# PCB-E21-CMB6.net
KiCad netlist of a schematic drawn in EAGLE
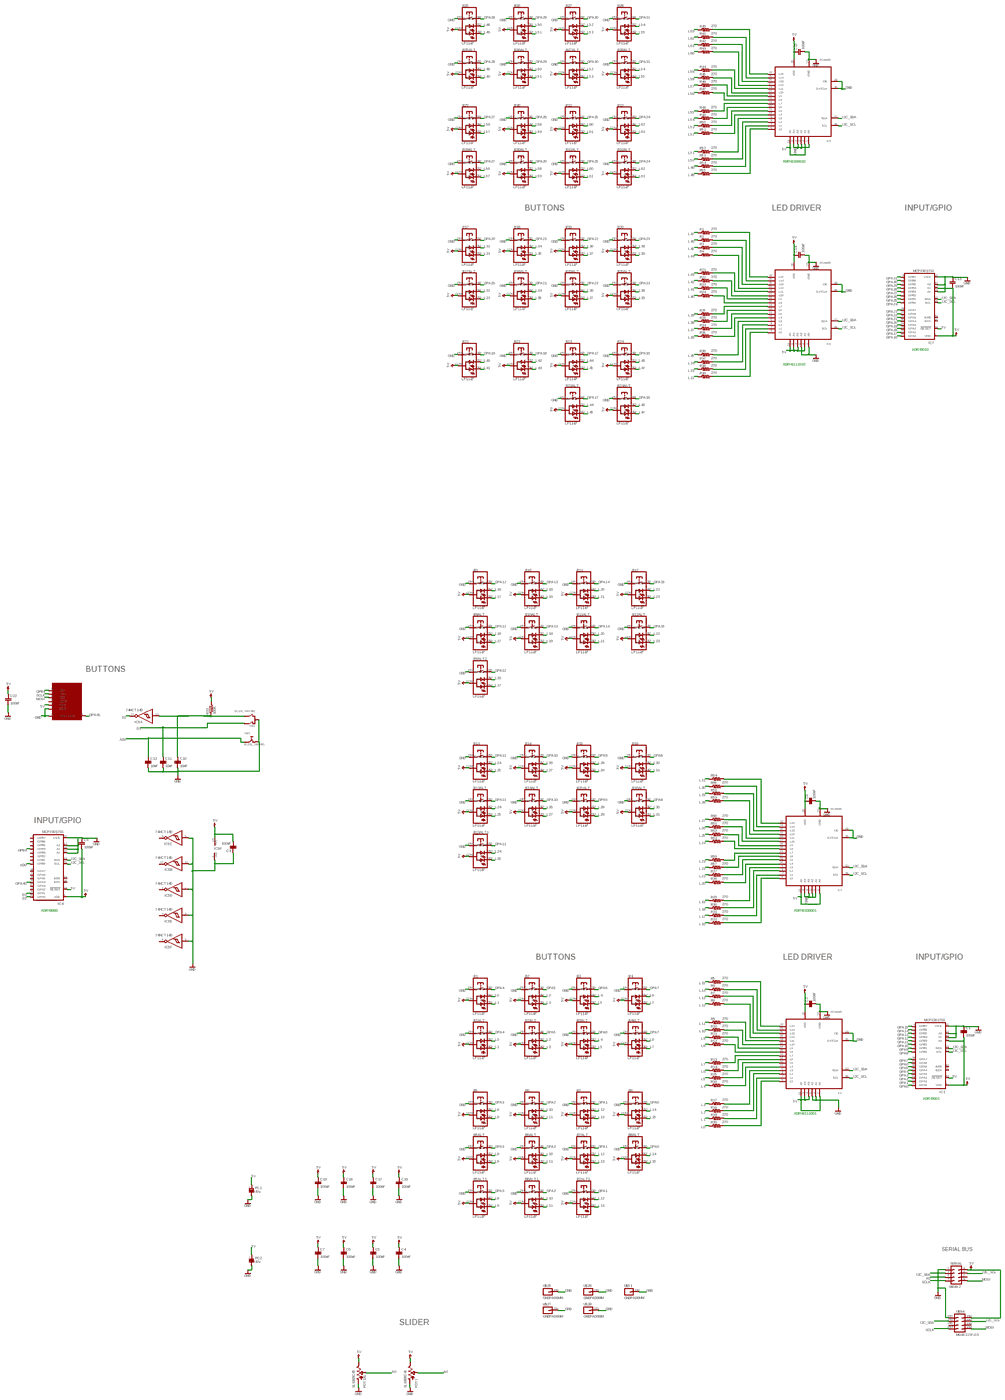
[diagram p0: schematic, sheet 1, overview]
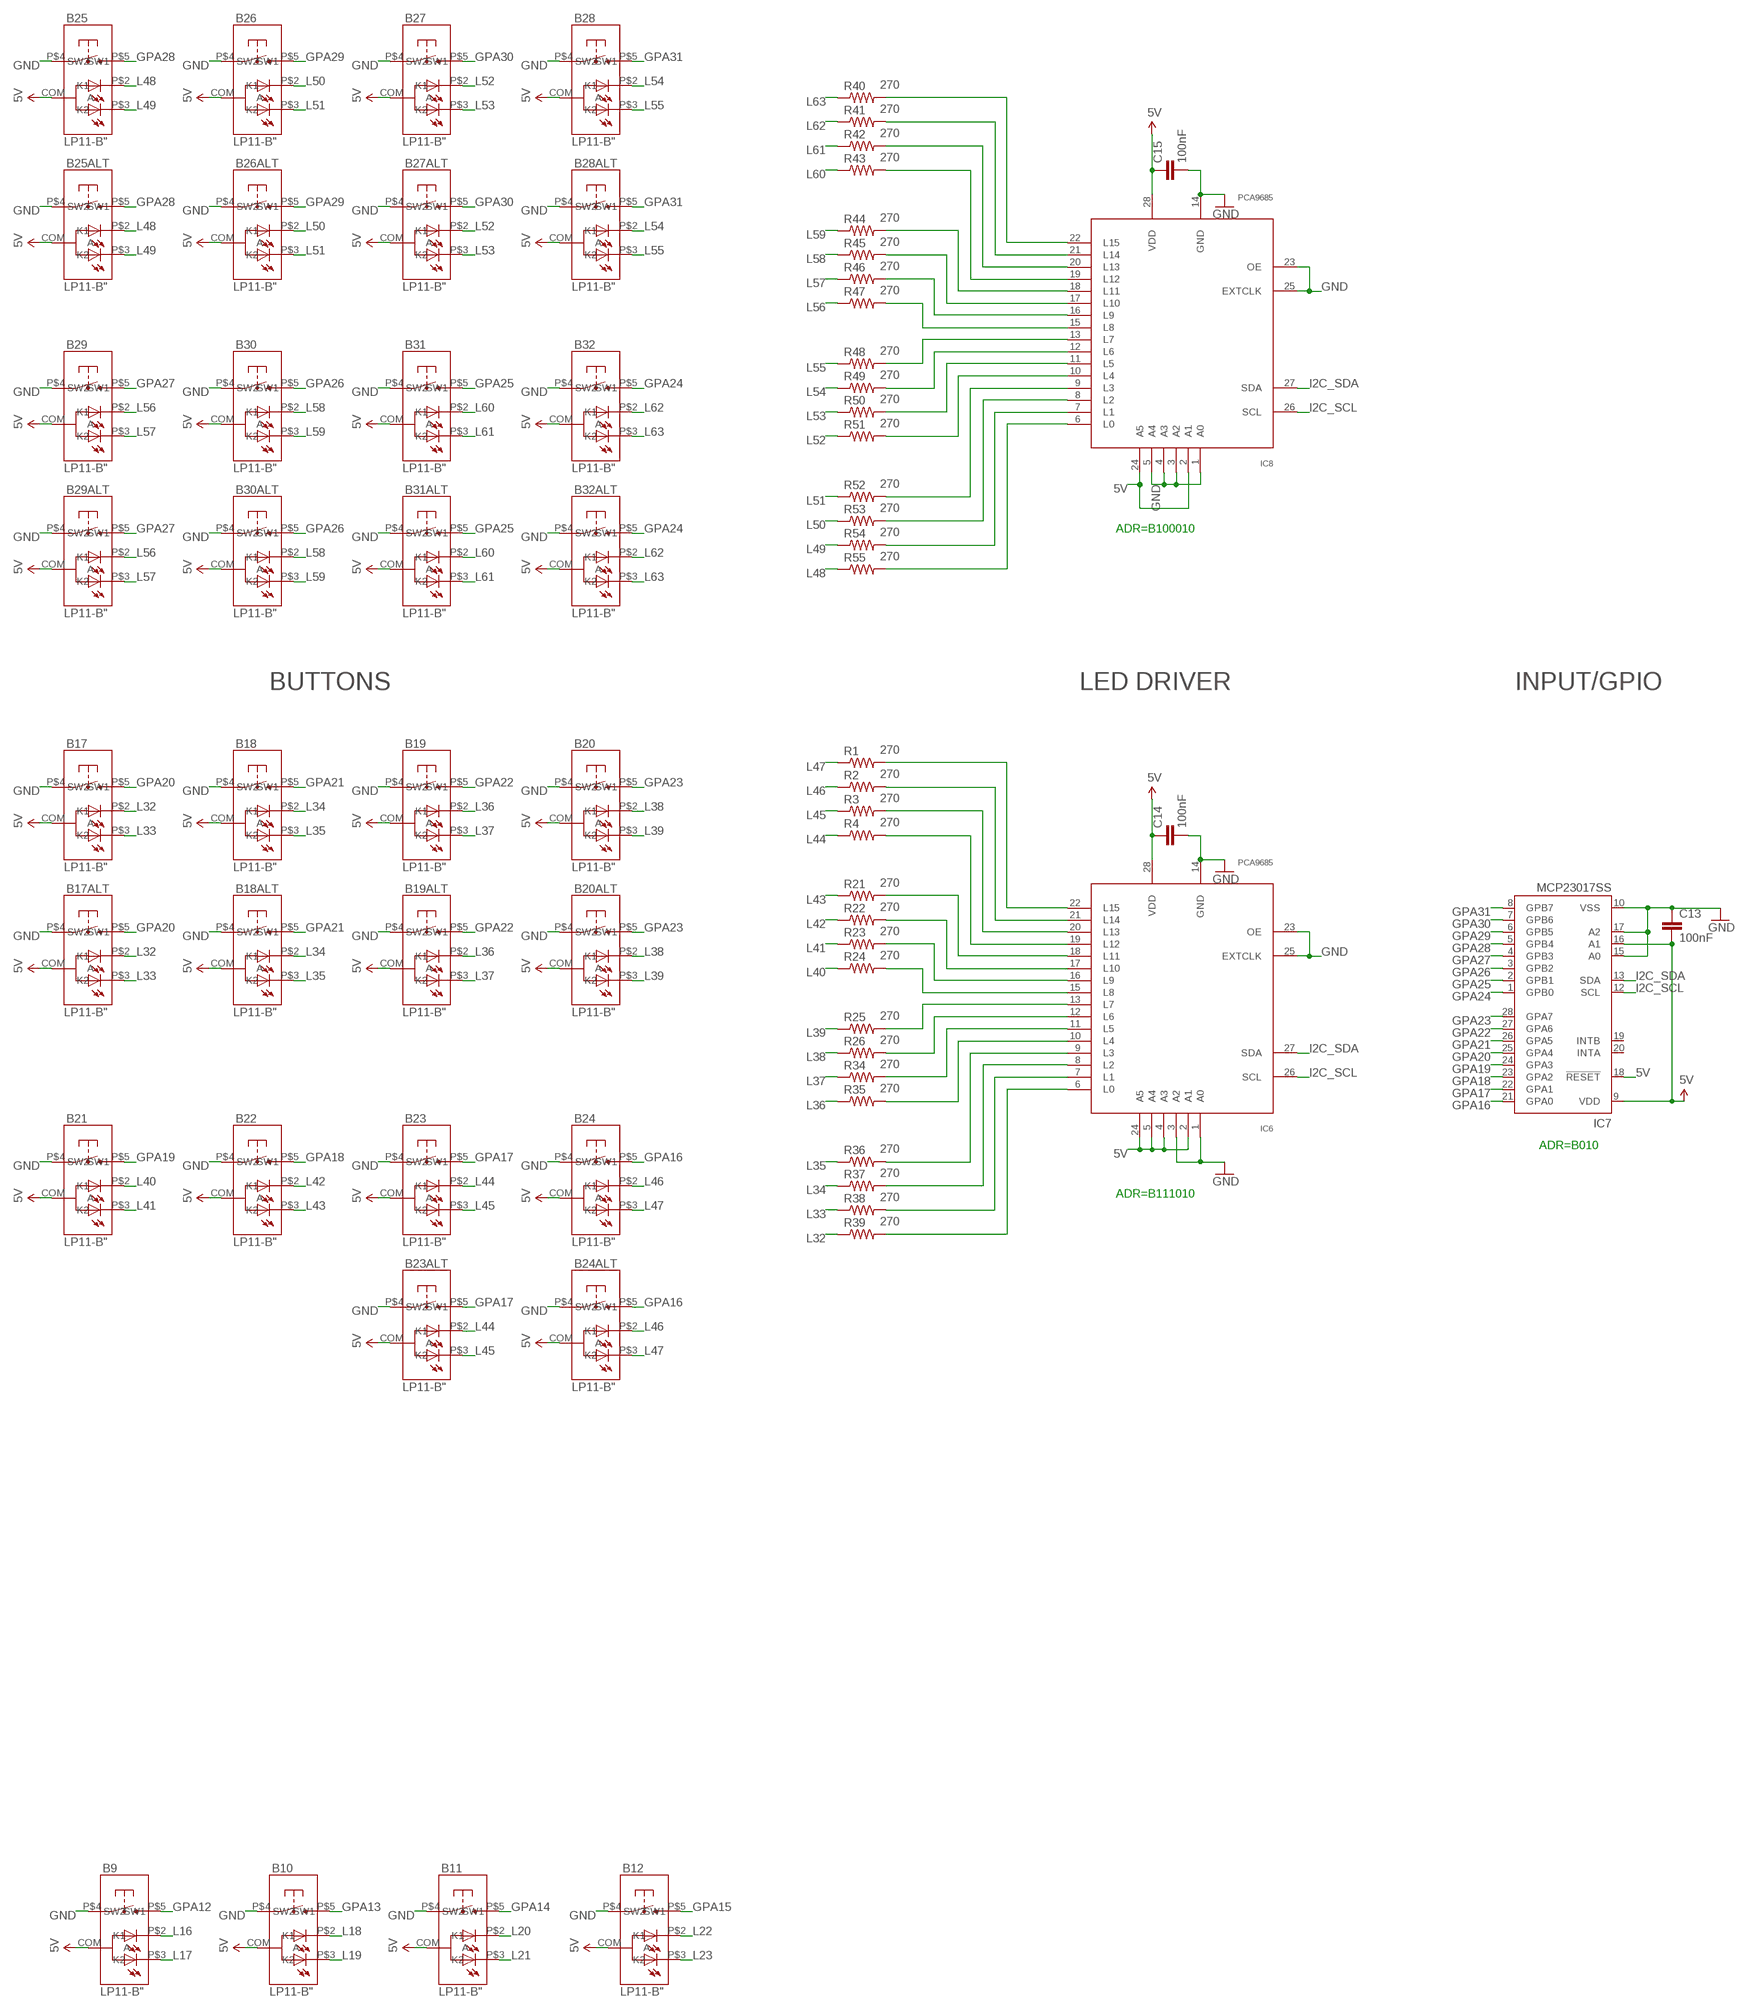
[diagram p1: schematic, sheet 1, part 1 of 5]
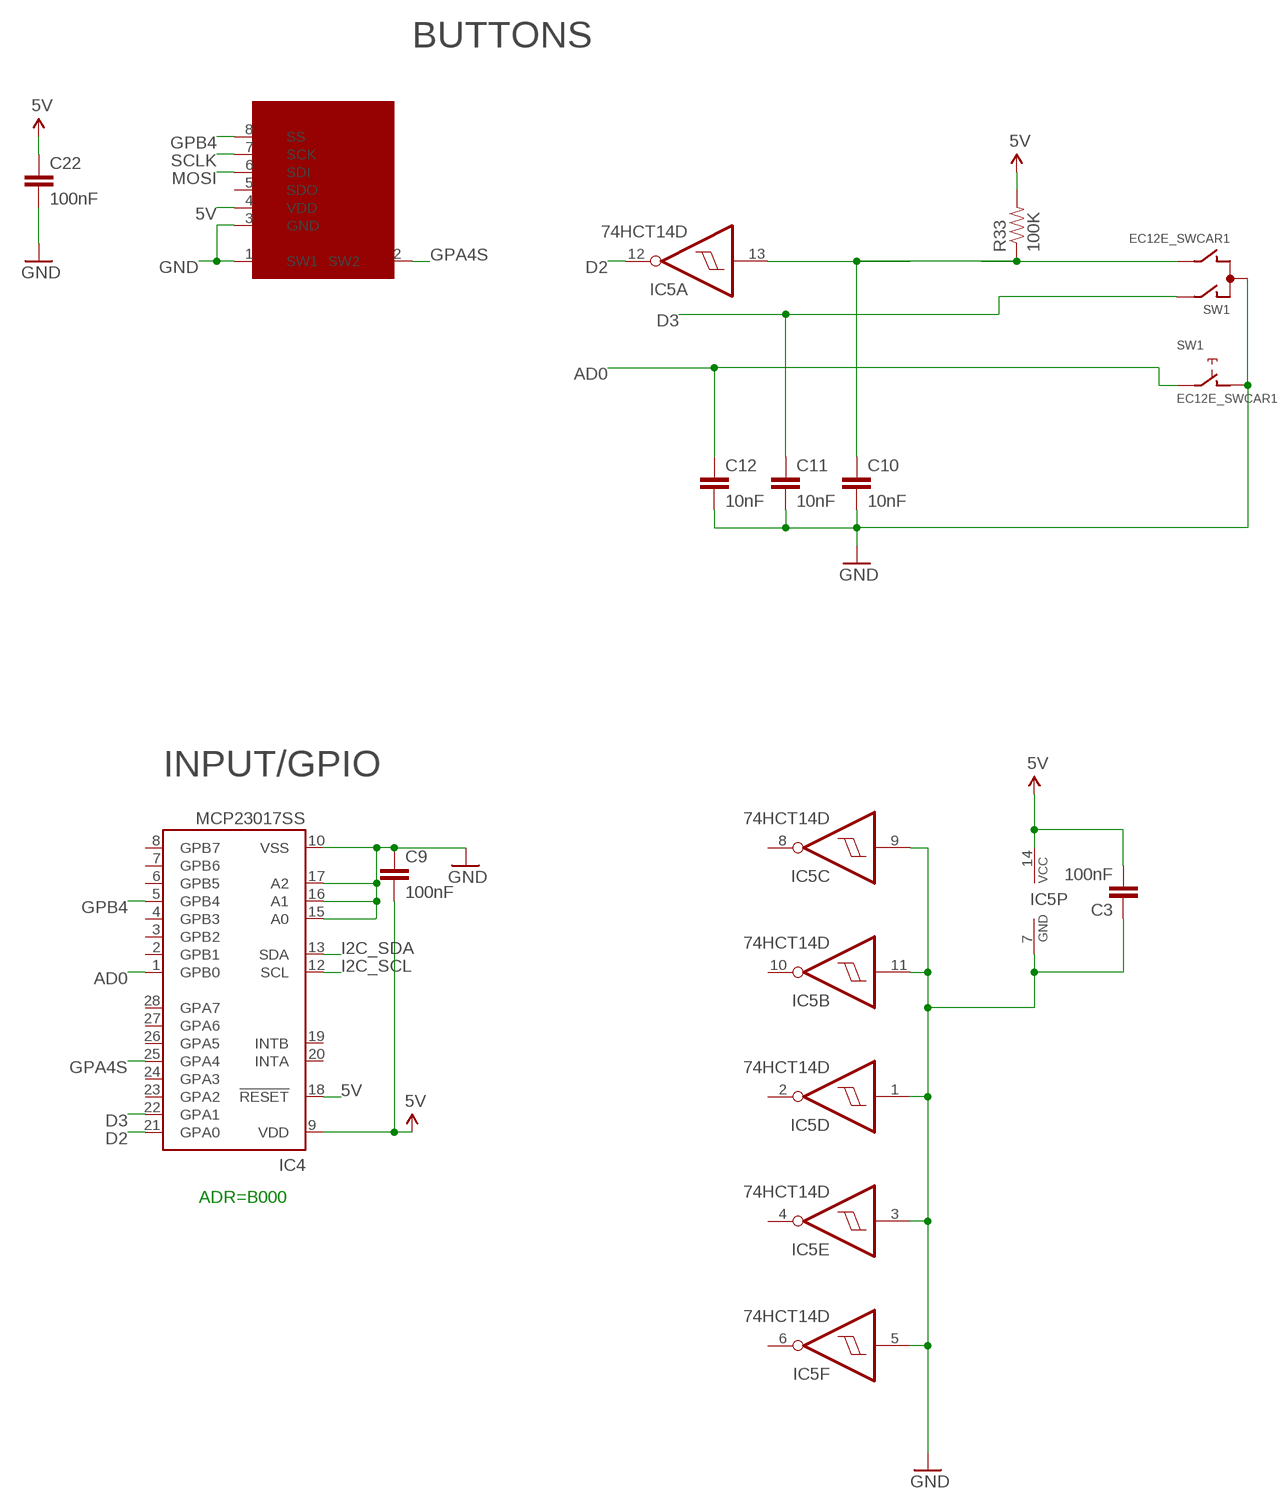
[diagram p2: schematic, sheet 1, part 2 of 5]
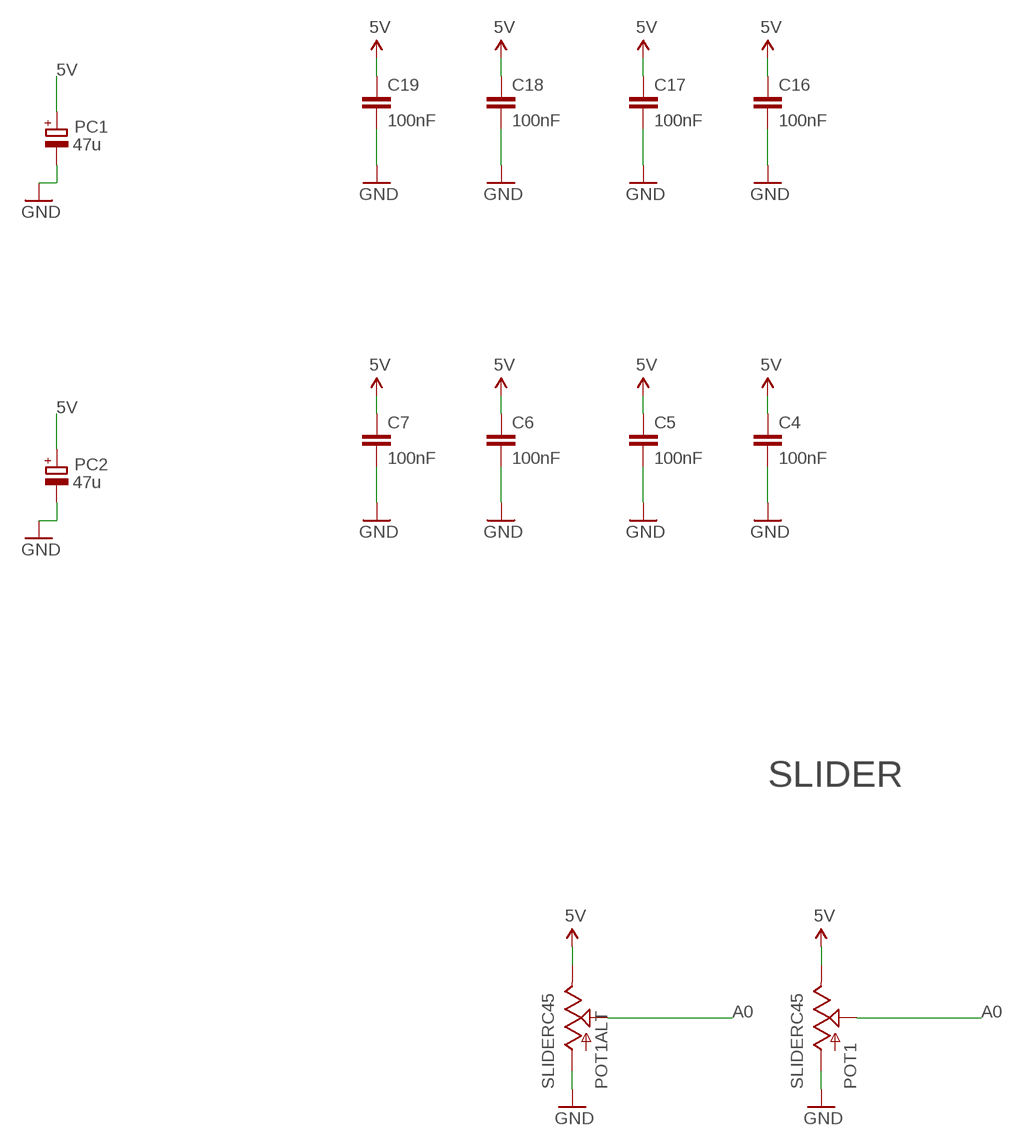
[diagram p3: schematic, sheet 1, part 3 of 5]
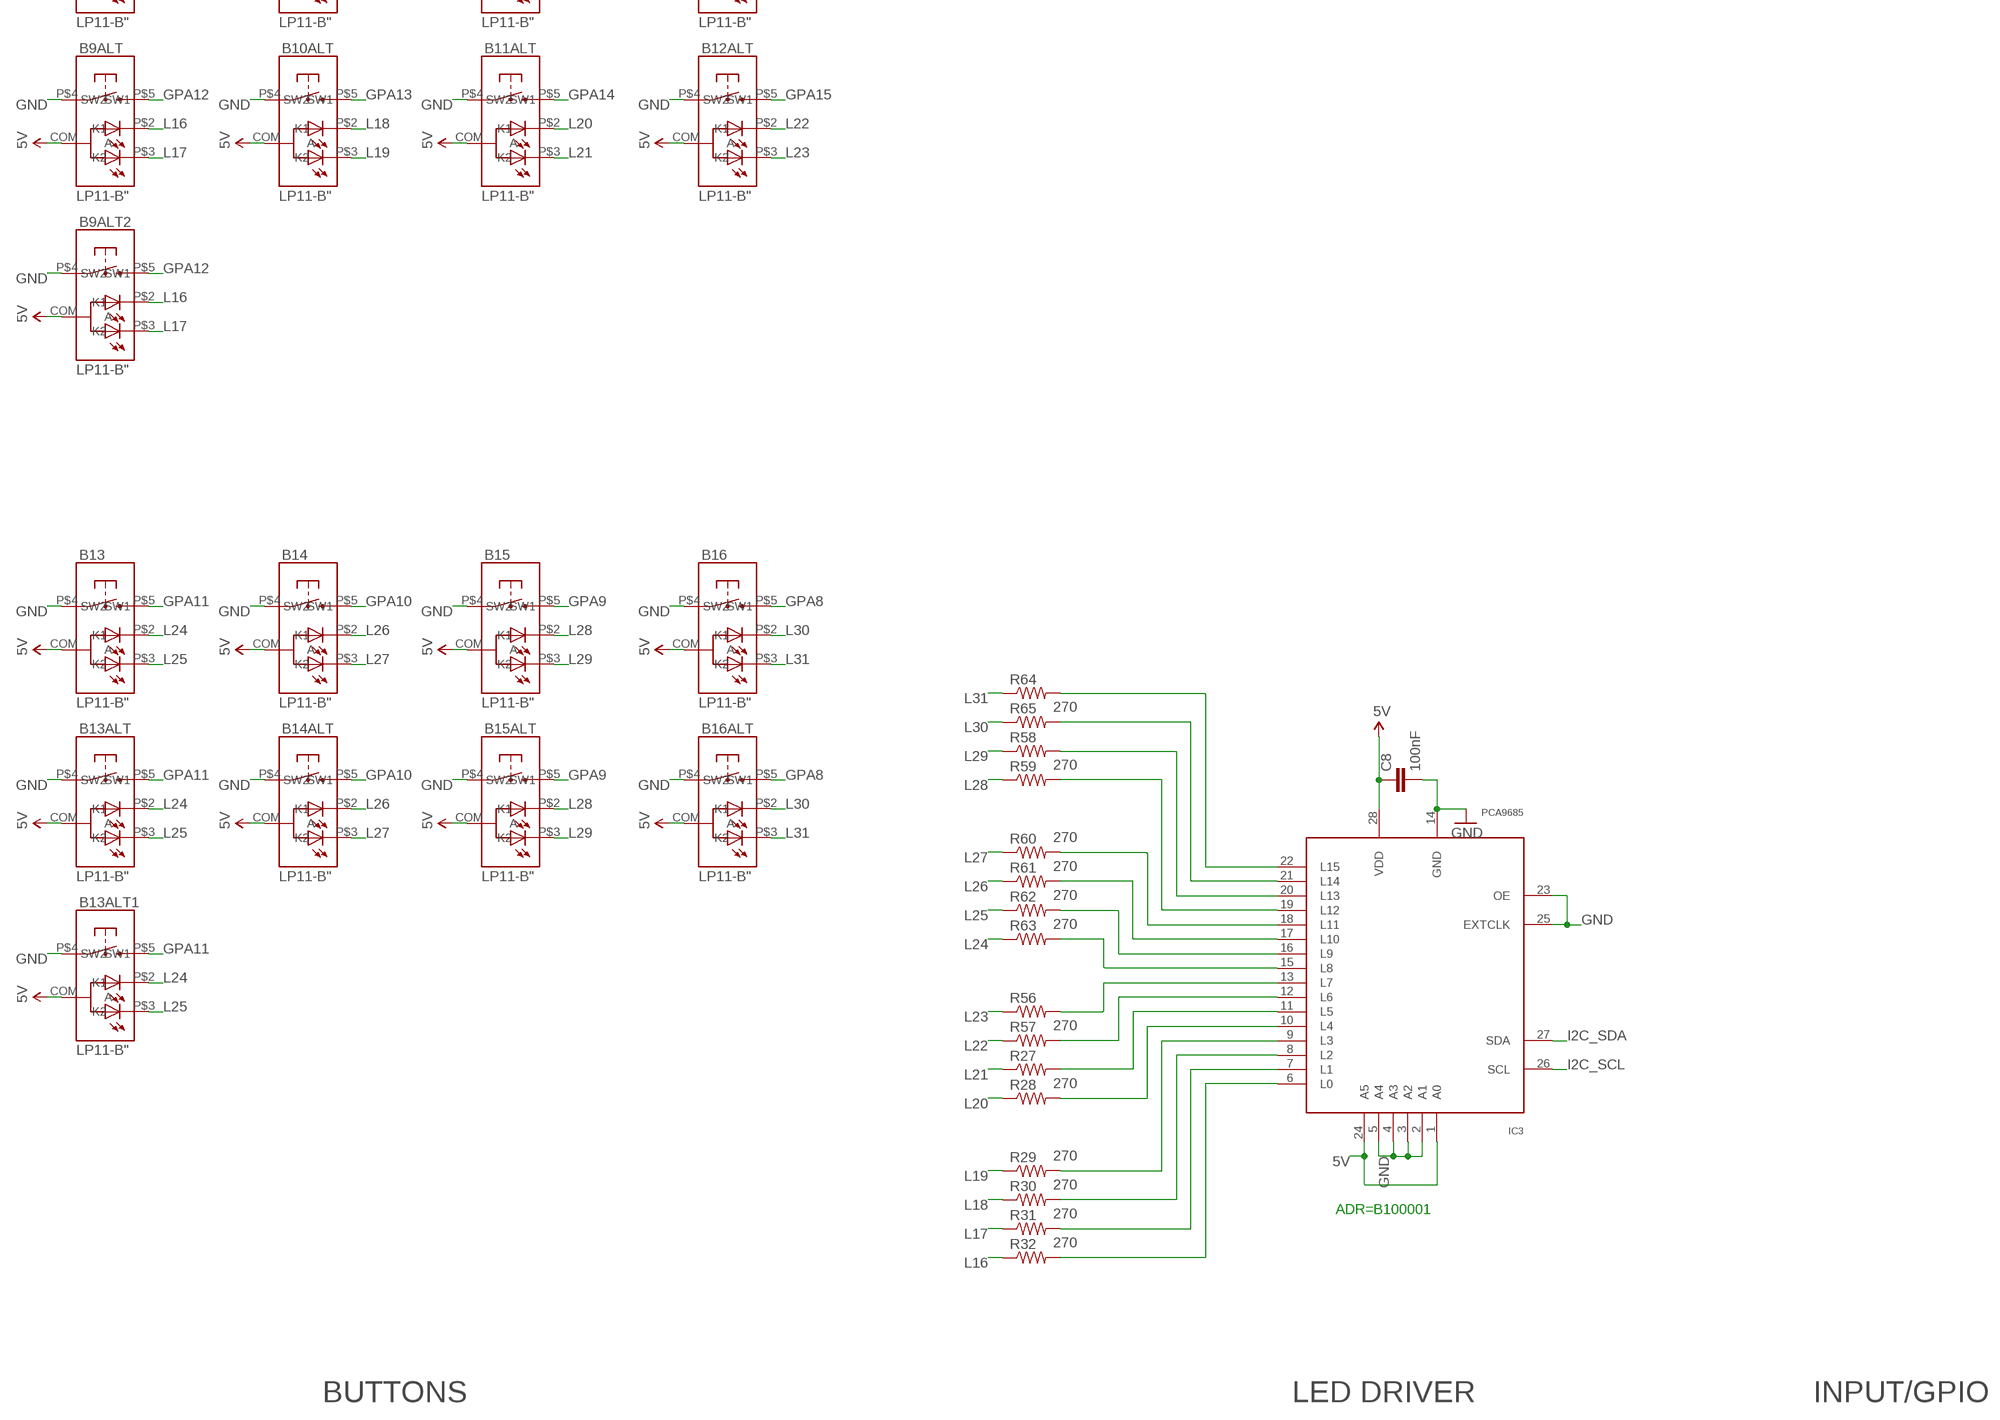
[diagram p4: schematic, sheet 1, part 4 of 5]
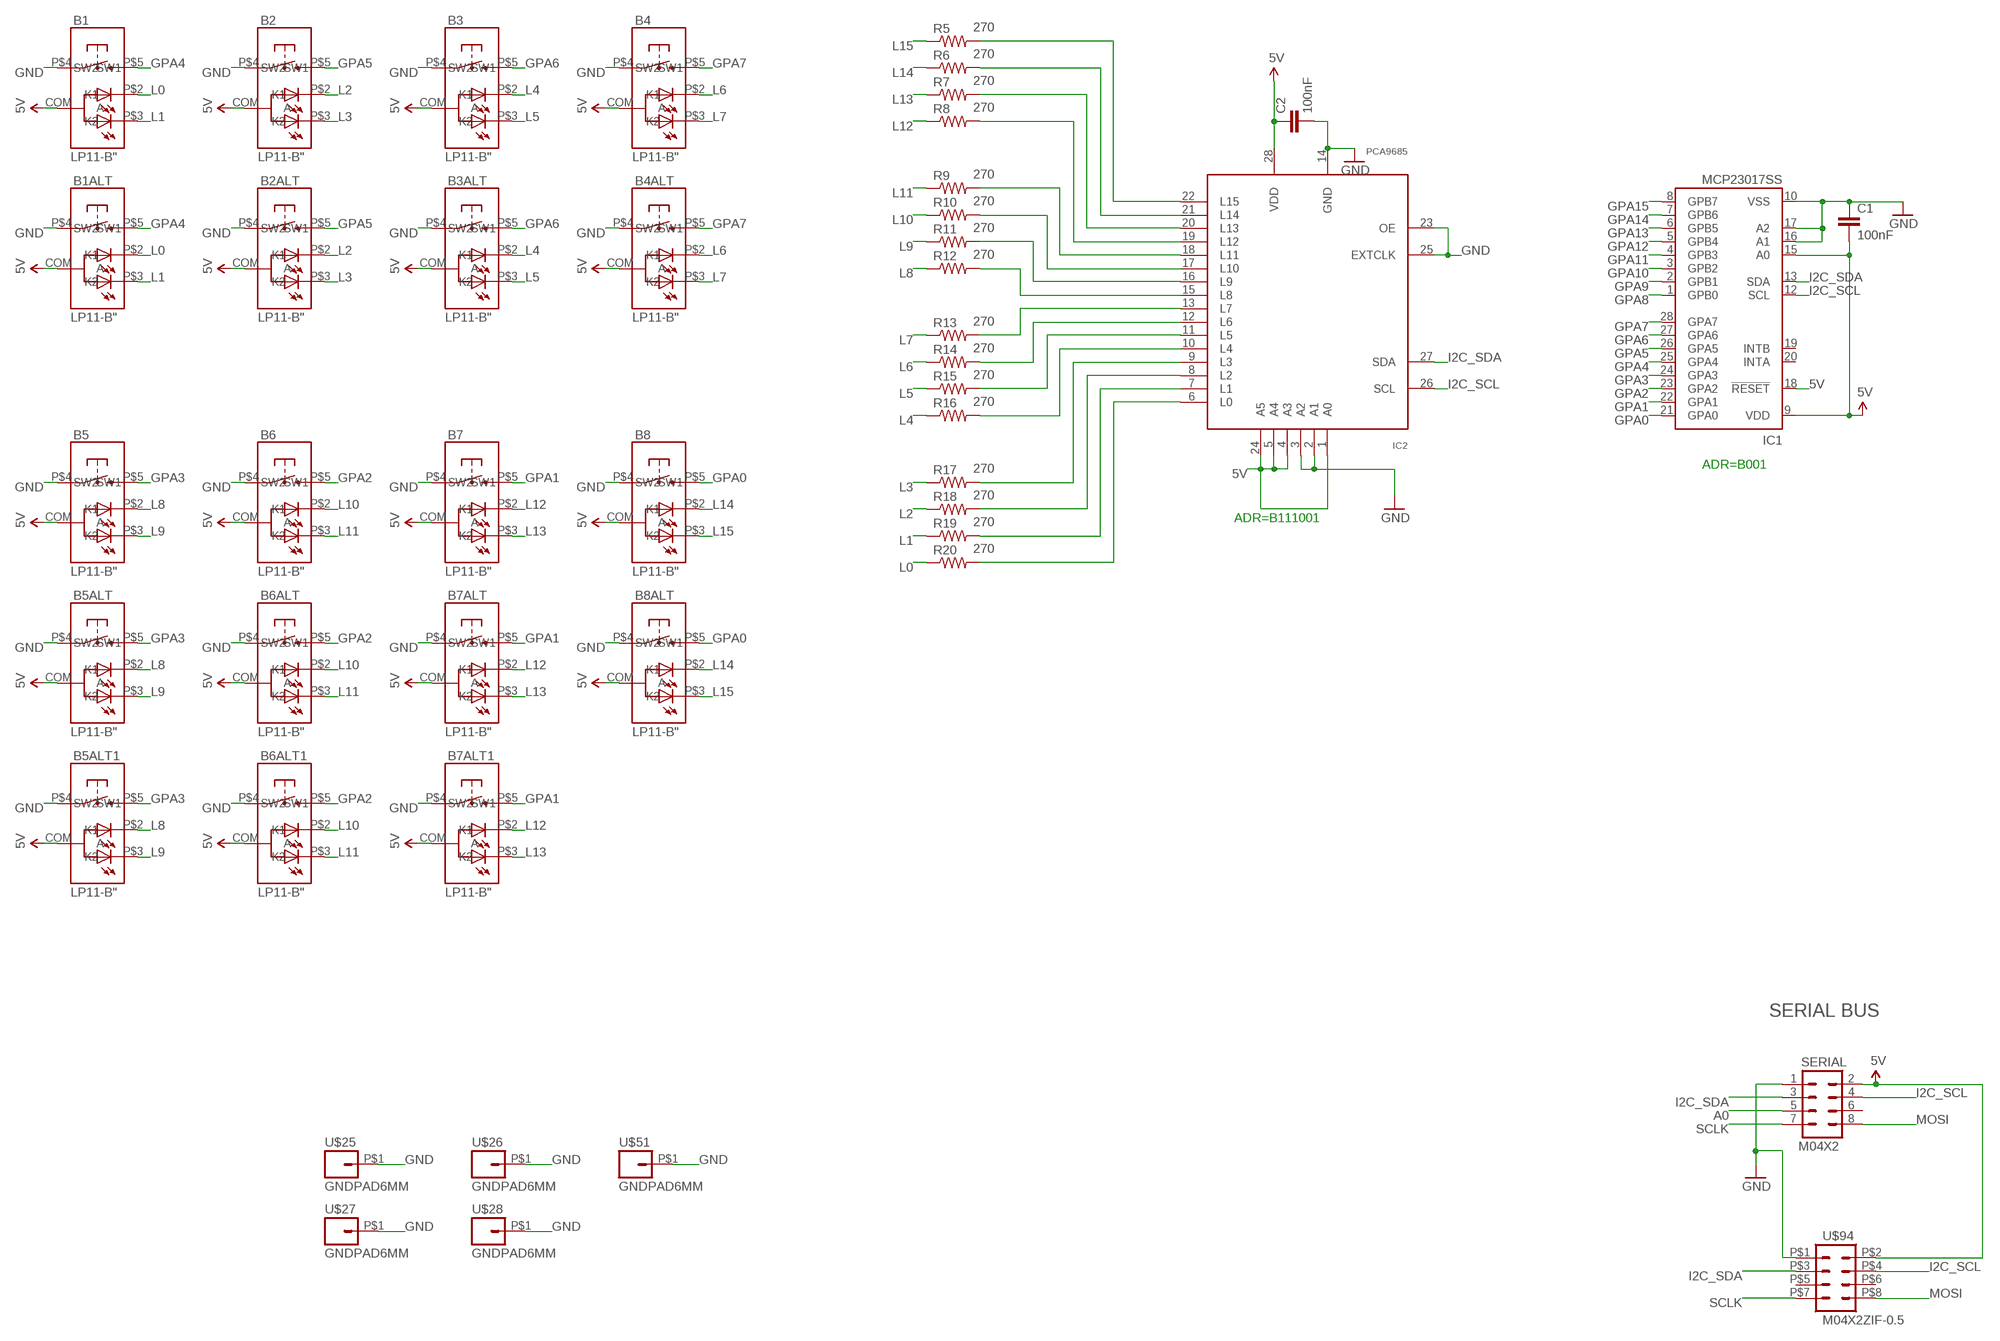
[diagram p5: schematic, sheet 1, part 5 of 5]

(export (version "E")
  (design (tool "Eeschema 10.0.6"))
  (components
    (comp (ref "B1")
      (value "LP11-B\"")
      (footprint "eagle-import:LP11")
      (libsource (lib "eagle-import") (part "LP11-B{dblquote}"))
    )
    (comp (ref "B1ALT")
      (value "LP11-B\"")
      (footprint "eagle-import:LP11")
      (libsource (lib "eagle-import") (part "LP11-B{dblquote}"))
    )
    (comp (ref "B2")
      (value "LP11-B\"")
      (footprint "eagle-import:LP11")
      (libsource (lib "eagle-import") (part "LP11-B{dblquote}"))
    )
    (comp (ref "B2ALT")
      (value "LP11-B\"")
      (footprint "eagle-import:LP11")
      (libsource (lib "eagle-import") (part "LP11-B{dblquote}"))
    )
    (comp (ref "B3")
      (value "LP11-B\"")
      (footprint "eagle-import:LP11")
      (libsource (lib "eagle-import") (part "LP11-B{dblquote}"))
    )
    (comp (ref "B3ALT")
      (value "LP11-B\"")
      (footprint "eagle-import:LP11")
      (libsource (lib "eagle-import") (part "LP11-B{dblquote}"))
    )
    (comp (ref "B4")
      (value "LP11-B\"")
      (footprint "eagle-import:LP11")
      (libsource (lib "eagle-import") (part "LP11-B{dblquote}"))
    )
    (comp (ref "B4ALT")
      (value "LP11-B\"")
      (footprint "eagle-import:LP11")
      (libsource (lib "eagle-import") (part "LP11-B{dblquote}"))
    )
    (comp (ref "B5")
      (value "LP11-B\"")
      (footprint "eagle-import:LP11")
      (libsource (lib "eagle-import") (part "LP11-B{dblquote}"))
    )
    (comp (ref "B5ALT")
      (value "LP11-B\"")
      (footprint "eagle-import:LP11")
      (libsource (lib "eagle-import") (part "LP11-B{dblquote}"))
    )
    (comp (ref "B5ALT1")
      (value "LP11-B\"")
      (footprint "eagle-import:LP11")
      (libsource (lib "eagle-import") (part "LP11-B{dblquote}"))
    )
    (comp (ref "B6")
      (value "LP11-B\"")
      (footprint "eagle-import:LP11")
      (libsource (lib "eagle-import") (part "LP11-B{dblquote}"))
    )
    (comp (ref "B6ALT")
      (value "LP11-B\"")
      (footprint "eagle-import:LP11")
      (libsource (lib "eagle-import") (part "LP11-B{dblquote}"))
    )
    (comp (ref "B6ALT1")
      (value "LP11-B\"")
      (footprint "eagle-import:LP11")
      (libsource (lib "eagle-import") (part "LP11-B{dblquote}"))
    )
    (comp (ref "B7")
      (value "LP11-B\"")
      (footprint "eagle-import:LP11")
      (libsource (lib "eagle-import") (part "LP11-B{dblquote}"))
    )
    (comp (ref "B7ALT")
      (value "LP11-B\"")
      (footprint "eagle-import:LP11")
      (libsource (lib "eagle-import") (part "LP11-B{dblquote}"))
    )
    (comp (ref "B7ALT1")
      (value "LP11-B\"")
      (footprint "eagle-import:LP11")
      (libsource (lib "eagle-import") (part "LP11-B{dblquote}"))
    )
    (comp (ref "B8")
      (value "LP11-B\"")
      (footprint "eagle-import:LP11")
      (libsource (lib "eagle-import") (part "LP11-B{dblquote}"))
    )
    (comp (ref "B8ALT")
      (value "LP11-B\"")
      (footprint "eagle-import:LP11")
      (libsource (lib "eagle-import") (part "LP11-B{dblquote}"))
    )
    (comp (ref "B9")
      (value "LP11-B\"")
      (footprint "eagle-import:LP11")
      (libsource (lib "eagle-import") (part "LP11-B{dblquote}"))
    )
    (comp (ref "B9ALT")
      (value "LP11-B\"")
      (footprint "eagle-import:LP11")
      (libsource (lib "eagle-import") (part "LP11-B{dblquote}"))
    )
    (comp (ref "B9ALT2")
      (value "LP11-B\"")
      (footprint "eagle-import:LP11")
      (libsource (lib "eagle-import") (part "LP11-B{dblquote}"))
    )
    (comp (ref "B10")
      (value "LP11-B\"")
      (footprint "eagle-import:LP11")
      (libsource (lib "eagle-import") (part "LP11-B{dblquote}"))
    )
    (comp (ref "B10ALT")
      (value "LP11-B\"")
      (footprint "eagle-import:LP11")
      (libsource (lib "eagle-import") (part "LP11-B{dblquote}"))
    )
    (comp (ref "B11")
      (value "LP11-B\"")
      (footprint "eagle-import:LP11")
      (libsource (lib "eagle-import") (part "LP11-B{dblquote}"))
    )
    (comp (ref "B11ALT")
      (value "LP11-B\"")
      (footprint "eagle-import:LP11")
      (libsource (lib "eagle-import") (part "LP11-B{dblquote}"))
    )
    (comp (ref "B12")
      (value "LP11-B\"")
      (footprint "eagle-import:LP11")
      (libsource (lib "eagle-import") (part "LP11-B{dblquote}"))
    )
    (comp (ref "B12ALT")
      (value "LP11-B\"")
      (footprint "eagle-import:LP11")
      (libsource (lib "eagle-import") (part "LP11-B{dblquote}"))
    )
    (comp (ref "B13")
      (value "LP11-B\"")
      (footprint "eagle-import:LP11")
      (libsource (lib "eagle-import") (part "LP11-B{dblquote}"))
    )
    (comp (ref "B13ALT")
      (value "LP11-B\"")
      (footprint "eagle-import:LP11")
      (libsource (lib "eagle-import") (part "LP11-B{dblquote}"))
    )
    (comp (ref "B13ALT1")
      (value "LP11-B\"")
      (footprint "eagle-import:LP11")
      (libsource (lib "eagle-import") (part "LP11-B{dblquote}"))
    )
    (comp (ref "B14")
      (value "LP11-B\"")
      (footprint "eagle-import:LP11")
      (libsource (lib "eagle-import") (part "LP11-B{dblquote}"))
    )
    (comp (ref "B14ALT")
      (value "LP11-B\"")
      (footprint "eagle-import:LP11")
      (libsource (lib "eagle-import") (part "LP11-B{dblquote}"))
    )
    (comp (ref "B15")
      (value "LP11-B\"")
      (footprint "eagle-import:LP11")
      (libsource (lib "eagle-import") (part "LP11-B{dblquote}"))
    )
    (comp (ref "B15ALT")
      (value "LP11-B\"")
      (footprint "eagle-import:LP11")
      (libsource (lib "eagle-import") (part "LP11-B{dblquote}"))
    )
    (comp (ref "B16")
      (value "LP11-B\"")
      (footprint "eagle-import:LP11")
      (libsource (lib "eagle-import") (part "LP11-B{dblquote}"))
    )
    (comp (ref "B16ALT")
      (value "LP11-B\"")
      (footprint "eagle-import:LP11")
      (libsource (lib "eagle-import") (part "LP11-B{dblquote}"))
    )
    (comp (ref "B17")
      (value "LP11-B\"")
      (footprint "eagle-import:LP11")
      (libsource (lib "eagle-import") (part "LP11-B{dblquote}"))
    )
    (comp (ref "B17ALT")
      (value "LP11-B\"")
      (footprint "eagle-import:LP11")
      (libsource (lib "eagle-import") (part "LP11-B{dblquote}"))
    )
    (comp (ref "B18")
      (value "LP11-B\"")
      (footprint "eagle-import:LP11")
      (libsource (lib "eagle-import") (part "LP11-B{dblquote}"))
    )
    (comp (ref "B18ALT")
      (value "LP11-B\"")
      (footprint "eagle-import:LP11")
      (libsource (lib "eagle-import") (part "LP11-B{dblquote}"))
    )
    (comp (ref "B19")
      (value "LP11-B\"")
      (footprint "eagle-import:LP11")
      (libsource (lib "eagle-import") (part "LP11-B{dblquote}"))
    )
    (comp (ref "B19ALT")
      (value "LP11-B\"")
      (footprint "eagle-import:LP11")
      (libsource (lib "eagle-import") (part "LP11-B{dblquote}"))
    )
    (comp (ref "B20")
      (value "LP11-B\"")
      (footprint "eagle-import:LP11")
      (libsource (lib "eagle-import") (part "LP11-B{dblquote}"))
    )
    (comp (ref "B20ALT")
      (value "LP11-B\"")
      (footprint "eagle-import:LP11")
      (libsource (lib "eagle-import") (part "LP11-B{dblquote}"))
    )
    (comp (ref "B21")
      (value "LP11-B\"")
      (footprint "eagle-import:LP11")
      (libsource (lib "eagle-import") (part "LP11-B{dblquote}"))
    )
    (comp (ref "B22")
      (value "LP11-B\"")
      (footprint "eagle-import:LP11")
      (libsource (lib "eagle-import") (part "LP11-B{dblquote}"))
    )
    (comp (ref "B23")
      (value "LP11-B\"")
      (footprint "eagle-import:LP11")
      (libsource (lib "eagle-import") (part "LP11-B{dblquote}"))
    )
    (comp (ref "B23ALT")
      (value "LP11-B\"")
      (footprint "eagle-import:LP11")
      (libsource (lib "eagle-import") (part "LP11-B{dblquote}"))
    )
    (comp (ref "B24")
      (value "LP11-B\"")
      (footprint "eagle-import:LP11")
      (libsource (lib "eagle-import") (part "LP11-B{dblquote}"))
    )
    (comp (ref "B24ALT")
      (value "LP11-B\"")
      (footprint "eagle-import:LP11")
      (libsource (lib "eagle-import") (part "LP11-B{dblquote}"))
    )
    (comp (ref "B25")
      (value "LP11-B\"")
      (footprint "eagle-import:LP11")
      (libsource (lib "eagle-import") (part "LP11-B{dblquote}"))
    )
    (comp (ref "B25ALT")
      (value "LP11-B\"")
      (footprint "eagle-import:LP11")
      (libsource (lib "eagle-import") (part "LP11-B{dblquote}"))
    )
    (comp (ref "B26")
      (value "LP11-B\"")
      (footprint "eagle-import:LP11")
      (libsource (lib "eagle-import") (part "LP11-B{dblquote}"))
    )
    (comp (ref "B26ALT")
      (value "LP11-B\"")
      (footprint "eagle-import:LP11")
      (libsource (lib "eagle-import") (part "LP11-B{dblquote}"))
    )
    (comp (ref "B27")
      (value "LP11-B\"")
      (footprint "eagle-import:LP11")
      (libsource (lib "eagle-import") (part "LP11-B{dblquote}"))
    )
    (comp (ref "B27ALT")
      (value "LP11-B\"")
      (footprint "eagle-import:LP11")
      (libsource (lib "eagle-import") (part "LP11-B{dblquote}"))
    )
    (comp (ref "B28")
      (value "LP11-B\"")
      (footprint "eagle-import:LP11")
      (libsource (lib "eagle-import") (part "LP11-B{dblquote}"))
    )
    (comp (ref "B28ALT")
      (value "LP11-B\"")
      (footprint "eagle-import:LP11")
      (libsource (lib "eagle-import") (part "LP11-B{dblquote}"))
    )
    (comp (ref "B29")
      (value "LP11-B\"")
      (footprint "eagle-import:LP11")
      (libsource (lib "eagle-import") (part "LP11-B{dblquote}"))
    )
    (comp (ref "B29ALT")
      (value "LP11-B\"")
      (footprint "eagle-import:LP11")
      (libsource (lib "eagle-import") (part "LP11-B{dblquote}"))
    )
    (comp (ref "B30")
      (value "LP11-B\"")
      (footprint "eagle-import:LP11")
      (libsource (lib "eagle-import") (part "LP11-B{dblquote}"))
    )
    (comp (ref "B30ALT")
      (value "LP11-B\"")
      (footprint "eagle-import:LP11")
      (libsource (lib "eagle-import") (part "LP11-B{dblquote}"))
    )
    (comp (ref "B31")
      (value "LP11-B\"")
      (footprint "eagle-import:LP11")
      (libsource (lib "eagle-import") (part "LP11-B{dblquote}"))
    )
    (comp (ref "B31ALT")
      (value "LP11-B\"")
      (footprint "eagle-import:LP11")
      (libsource (lib "eagle-import") (part "LP11-B{dblquote}"))
    )
    (comp (ref "B32")
      (value "LP11-B\"")
      (footprint "eagle-import:LP11")
      (libsource (lib "eagle-import") (part "LP11-B{dblquote}"))
    )
    (comp (ref "B32ALT")
      (value "LP11-B\"")
      (footprint "eagle-import:LP11")
      (libsource (lib "eagle-import") (part "LP11-B{dblquote}"))
    )
    (comp (ref "C1")
      (value "100nF")
      (footprint "eagle-import:0603-CAP")
      (libsource (lib "eagle-import") (part "CAP0603-CAP"))
    )
    (comp (ref "C2")
      (value "100nF")
      (footprint "eagle-import:0603-CAP")
      (libsource (lib "eagle-import") (part "CAP0603-CAP"))
    )
    (comp (ref "C3")
      (value "100nF")
      (footprint "eagle-import:0603-CAP")
      (libsource (lib "eagle-import") (part "CAP0603-CAP"))
    )
    (comp (ref "C4")
      (value "100nF")
      (footprint "eagle-import:0603-CAP")
      (libsource (lib "eagle-import") (part "CAP0603-CAP"))
    )
    (comp (ref "C5")
      (value "100nF")
      (footprint "eagle-import:0603-CAP")
      (libsource (lib "eagle-import") (part "CAP0603-CAP"))
    )
    (comp (ref "C6")
      (value "100nF")
      (footprint "eagle-import:0603-CAP")
      (libsource (lib "eagle-import") (part "CAP0603-CAP"))
    )
    (comp (ref "C7")
      (value "100nF")
      (footprint "eagle-import:0603-CAP")
      (libsource (lib "eagle-import") (part "CAP0603-CAP"))
    )
    (comp (ref "C8")
      (value "100nF")
      (footprint "eagle-import:0603-CAP")
      (libsource (lib "eagle-import") (part "CAP0603-CAP"))
    )
    (comp (ref "C9")
      (value "100nF")
      (footprint "eagle-import:0603-CAP")
      (libsource (lib "eagle-import") (part "CAP0603-CAP"))
    )
    (comp (ref "C10")
      (value "10nF")
      (footprint "eagle-import:0603-CAP")
      (libsource (lib "eagle-import") (part "CAP0603-CAP"))
    )
    (comp (ref "C11")
      (value "10nF")
      (footprint "eagle-import:0603-CAP")
      (libsource (lib "eagle-import") (part "CAP0603-CAP"))
    )
    (comp (ref "C12")
      (value "10nF")
      (footprint "eagle-import:0603-CAP")
      (libsource (lib "eagle-import") (part "CAP0603-CAP"))
    )
    (comp (ref "C13")
      (value "100nF")
      (footprint "eagle-import:0603-CAP")
      (libsource (lib "eagle-import") (part "CAP0603-CAP"))
    )
    (comp (ref "C14")
      (value "100nF")
      (footprint "eagle-import:0603-CAP")
      (libsource (lib "eagle-import") (part "CAP0603-CAP"))
    )
    (comp (ref "C15")
      (value "100nF")
      (footprint "eagle-import:0603-CAP")
      (libsource (lib "eagle-import") (part "CAP0603-CAP"))
    )
    (comp (ref "C16")
      (value "100nF")
      (footprint "eagle-import:0603-CAP")
      (libsource (lib "eagle-import") (part "CAP0603-CAP"))
    )
    (comp (ref "C17")
      (value "100nF")
      (footprint "eagle-import:0603-CAP")
      (libsource (lib "eagle-import") (part "CAP0603-CAP"))
    )
    (comp (ref "C18")
      (value "100nF")
      (footprint "eagle-import:0603-CAP")
      (libsource (lib "eagle-import") (part "CAP0603-CAP"))
    )
    (comp (ref "C19")
      (value "100nF")
      (footprint "eagle-import:0603-CAP")
      (libsource (lib "eagle-import") (part "CAP0603-CAP"))
    )
    (comp (ref "C22")
      (value "100nF")
      (footprint "eagle-import:0603-CAP")
      (libsource (lib "eagle-import") (part "CAP0603-CAP"))
    )
    (comp (ref "IC1")
      (value "MCP23017SS")
      (footprint "eagle-import:SSOP28")
      (fields
        (field (name "MF") "MICROCHIP")
        (field (name "MPN") "MCP23017-E/SS")
        (field (name "MPN_1") "MCP23017-E/SS")
        (field (name "OC_FARNELL") "1467674")
        (field (name "OC_NEWARK") "31K2960")
      )
      (libsource (lib "eagle-import") (part "MCP23017SS"))
    )
    (comp (ref "IC2")
      (value "PCA9685")
      (footprint "eagle-import:TSSOP28")
      (libsource (lib "eagle-import") (part "PCA9685"))
    )
    (comp (ref "IC3")
      (value "PCA9685")
      (footprint "eagle-import:TSSOP28")
      (libsource (lib "eagle-import") (part "PCA9685"))
    )
    (comp (ref "IC4")
      (value "MCP23017SS")
      (footprint "eagle-import:SSOP28")
      (fields
        (field (name "MF") "MICROCHIP")
        (field (name "MPN") "MCP23017-E/SS")
        (field (name "MPN_1") "MCP23017-E/SS")
        (field (name "OC_FARNELL") "1467674")
        (field (name "OC_NEWARK") "31K2960")
      )
      (libsource (lib "eagle-import") (part "MCP23017SS"))
    )
    (comp (ref "IC5")
      (value "74HCT14D")
      (footprint "eagle-import:SO14")
      (libsource (lib "eagle-import") (part "7414DHCT"))
    )
    (comp (ref "IC6")
      (value "PCA9685")
      (footprint "eagle-import:TSSOP28")
      (libsource (lib "eagle-import") (part "PCA9685"))
    )
    (comp (ref "IC7")
      (value "MCP23017SS")
      (footprint "eagle-import:SSOP28")
      (fields
        (field (name "MF") "MICROCHIP")
        (field (name "MPN") "MCP23017-E/SS")
        (field (name "MPN_1") "MCP23017-E/SS")
        (field (name "OC_FARNELL") "1467674")
        (field (name "OC_NEWARK") "31K2960")
      )
      (libsource (lib "eagle-import") (part "MCP23017SS"))
    )
    (comp (ref "IC8")
      (value "PCA9685")
      (footprint "eagle-import:TSSOP28")
      (libsource (lib "eagle-import") (part "PCA9685"))
    )
    (comp (ref "PC1")
      (value "47u")
      (footprint "eagle-import:PANASONIC_D")
      (libsource (lib "eagle-import") (part "CPOL-EUD"))
    )
    (comp (ref "PC2")
      (value "47u")
      (footprint "eagle-import:PANASONIC_D")
      (libsource (lib "eagle-import") (part "CPOL-EUD"))
    )
    (comp (ref "POT1")
      (value "SLIDERC45")
      (footprint "eagle-import:SLIDER45-CAR1")
      (libsource (lib "eagle-import") (part "SLIDERC45"))
    )
    (comp (ref "POT1ALT")
      (value "SLIDERC45")
      (footprint "eagle-import:SLIDER45-CAR1")
      (libsource (lib "eagle-import") (part "SLIDERC45"))
    )
    (comp (ref "R1")
      (value "270")
      (footprint "eagle-import:0603-RES")
      (libsource (lib "eagle-import") (part "RESISTOR0603-RES"))
    )
    (comp (ref "R2")
      (value "270")
      (footprint "eagle-import:0603-RES")
      (libsource (lib "eagle-import") (part "RESISTOR0603-RES"))
    )
    (comp (ref "R3")
      (value "270")
      (footprint "eagle-import:0603-RES")
      (libsource (lib "eagle-import") (part "RESISTOR0603-RES"))
    )
    (comp (ref "R4")
      (value "270")
      (footprint "eagle-import:0603-RES")
      (libsource (lib "eagle-import") (part "RESISTOR0603-RES"))
    )
    (comp (ref "R5")
      (value "270")
      (footprint "eagle-import:0603-RES")
      (libsource (lib "eagle-import") (part "RESISTOR0603-RES"))
    )
    (comp (ref "R6")
      (value "270")
      (footprint "eagle-import:0603-RES")
      (libsource (lib "eagle-import") (part "RESISTOR0603-RES"))
    )
    (comp (ref "R7")
      (value "270")
      (footprint "eagle-import:0603-RES")
      (libsource (lib "eagle-import") (part "RESISTOR0603-RES"))
    )
    (comp (ref "R8")
      (value "270")
      (footprint "eagle-import:0603-RES")
      (libsource (lib "eagle-import") (part "RESISTOR0603-RES"))
    )
    (comp (ref "R9")
      (value "270")
      (footprint "eagle-import:0603-RES")
      (libsource (lib "eagle-import") (part "RESISTOR0603-RES"))
    )
    (comp (ref "R10")
      (value "270")
      (footprint "eagle-import:0603-RES")
      (libsource (lib "eagle-import") (part "RESISTOR0603-RES"))
    )
    (comp (ref "R11")
      (value "270")
      (footprint "eagle-import:0603-RES")
      (libsource (lib "eagle-import") (part "RESISTOR0603-RES"))
    )
    (comp (ref "R12")
      (value "270")
      (footprint "eagle-import:0603-RES")
      (libsource (lib "eagle-import") (part "RESISTOR0603-RES"))
    )
    (comp (ref "R13")
      (value "270")
      (footprint "eagle-import:0603-RES")
      (libsource (lib "eagle-import") (part "RESISTOR0603-RES"))
    )
    (comp (ref "R14")
      (value "270")
      (footprint "eagle-import:0603-RES")
      (libsource (lib "eagle-import") (part "RESISTOR0603-RES"))
    )
    (comp (ref "R15")
      (value "270")
      (footprint "eagle-import:0603-RES")
      (libsource (lib "eagle-import") (part "RESISTOR0603-RES"))
    )
    (comp (ref "R16")
      (value "270")
      (footprint "eagle-import:0603-RES")
      (libsource (lib "eagle-import") (part "RESISTOR0603-RES"))
    )
    (comp (ref "R17")
      (value "270")
      (footprint "eagle-import:0603-RES")
      (libsource (lib "eagle-import") (part "RESISTOR0603-RES"))
    )
    (comp (ref "R18")
      (value "270")
      (footprint "eagle-import:0603-RES")
      (libsource (lib "eagle-import") (part "RESISTOR0603-RES"))
    )
    (comp (ref "R19")
      (value "270")
      (footprint "eagle-import:0603-RES")
      (libsource (lib "eagle-import") (part "RESISTOR0603-RES"))
    )
    (comp (ref "R20")
      (value "270")
      (footprint "eagle-import:0603-RES")
      (libsource (lib "eagle-import") (part "RESISTOR0603-RES"))
    )
    (comp (ref "R21")
      (value "270")
      (footprint "eagle-import:0603-RES")
      (libsource (lib "eagle-import") (part "RESISTOR0603-RES"))
    )
    (comp (ref "R22")
      (value "270")
      (footprint "eagle-import:0603-RES")
      (libsource (lib "eagle-import") (part "RESISTOR0603-RES"))
    )
    (comp (ref "R23")
      (value "270")
      (footprint "eagle-import:0603-RES")
      (libsource (lib "eagle-import") (part "RESISTOR0603-RES"))
    )
    (comp (ref "R24")
      (value "270")
      (footprint "eagle-import:0603-RES")
      (libsource (lib "eagle-import") (part "RESISTOR0603-RES"))
    )
    (comp (ref "R25")
      (value "270")
      (footprint "eagle-import:0603-RES")
      (libsource (lib "eagle-import") (part "RESISTOR0603-RES"))
    )
    (comp (ref "R26")
      (value "270")
      (footprint "eagle-import:0603-RES")
      (libsource (lib "eagle-import") (part "RESISTOR0603-RES"))
    )
    (comp (ref "R27")
      (value "270")
      (footprint "eagle-import:0603-RES")
      (libsource (lib "eagle-import") (part "RESISTOR0603-RES"))
    )
    (comp (ref "R28")
      (value "270")
      (footprint "eagle-import:0603-RES")
      (libsource (lib "eagle-import") (part "RESISTOR0603-RES"))
    )
    (comp (ref "R29")
      (value "270")
      (footprint "eagle-import:0603-RES")
      (libsource (lib "eagle-import") (part "RESISTOR0603-RES"))
    )
    (comp (ref "R30")
      (value "270")
      (footprint "eagle-import:0603-RES")
      (libsource (lib "eagle-import") (part "RESISTOR0603-RES"))
    )
    (comp (ref "R31")
      (value "270")
      (footprint "eagle-import:0603-RES")
      (libsource (lib "eagle-import") (part "RESISTOR0603-RES"))
    )
    (comp (ref "R32")
      (value "270")
      (footprint "eagle-import:0603-RES")
      (libsource (lib "eagle-import") (part "RESISTOR0603-RES"))
    )
    (comp (ref "R33")
      (value "100K")
      (footprint "eagle-import:0603-RES")
      (libsource (lib "eagle-import") (part "RESISTOR0603-RES"))
    )
    (comp (ref "R34")
      (value "270")
      (footprint "eagle-import:0603-RES")
      (libsource (lib "eagle-import") (part "RESISTOR0603-RES"))
    )
    (comp (ref "R35")
      (value "270")
      (footprint "eagle-import:0603-RES")
      (libsource (lib "eagle-import") (part "RESISTOR0603-RES"))
    )
    (comp (ref "R36")
      (value "270")
      (footprint "eagle-import:0603-RES")
      (libsource (lib "eagle-import") (part "RESISTOR0603-RES"))
    )
    (comp (ref "R37")
      (value "270")
      (footprint "eagle-import:0603-RES")
      (libsource (lib "eagle-import") (part "RESISTOR0603-RES"))
    )
    (comp (ref "R38")
      (value "270")
      (footprint "eagle-import:0603-RES")
      (libsource (lib "eagle-import") (part "RESISTOR0603-RES"))
    )
    (comp (ref "R39")
      (value "270")
      (footprint "eagle-import:0603-RES")
      (libsource (lib "eagle-import") (part "RESISTOR0603-RES"))
    )
    (comp (ref "R40")
      (value "270")
      (footprint "eagle-import:0603-RES")
      (libsource (lib "eagle-import") (part "RESISTOR0603-RES"))
    )
    (comp (ref "R41")
      (value "270")
      (footprint "eagle-import:0603-RES")
      (libsource (lib "eagle-import") (part "RESISTOR0603-RES"))
    )
    (comp (ref "R42")
      (value "270")
      (footprint "eagle-import:0603-RES")
      (libsource (lib "eagle-import") (part "RESISTOR0603-RES"))
    )
    (comp (ref "R43")
      (value "270")
      (footprint "eagle-import:0603-RES")
      (libsource (lib "eagle-import") (part "RESISTOR0603-RES"))
    )
    (comp (ref "R44")
      (value "270")
      (footprint "eagle-import:0603-RES")
      (libsource (lib "eagle-import") (part "RESISTOR0603-RES"))
    )
    (comp (ref "R45")
      (value "270")
      (footprint "eagle-import:0603-RES")
      (libsource (lib "eagle-import") (part "RESISTOR0603-RES"))
    )
    (comp (ref "R46")
      (value "270")
      (footprint "eagle-import:0603-RES")
      (libsource (lib "eagle-import") (part "RESISTOR0603-RES"))
    )
    (comp (ref "R47")
      (value "270")
      (footprint "eagle-import:0603-RES")
      (libsource (lib "eagle-import") (part "RESISTOR0603-RES"))
    )
    (comp (ref "R48")
      (value "270")
      (footprint "eagle-import:0603-RES")
      (libsource (lib "eagle-import") (part "RESISTOR0603-RES"))
    )
    (comp (ref "R49")
      (value "270")
      (footprint "eagle-import:0603-RES")
      (libsource (lib "eagle-import") (part "RESISTOR0603-RES"))
    )
    (comp (ref "R50")
      (value "270")
      (footprint "eagle-import:0603-RES")
      (libsource (lib "eagle-import") (part "RESISTOR0603-RES"))
    )
    (comp (ref "R51")
      (value "270")
      (footprint "eagle-import:0603-RES")
      (libsource (lib "eagle-import") (part "RESISTOR0603-RES"))
    )
    (comp (ref "R52")
      (value "270")
      (footprint "eagle-import:0603-RES")
      (libsource (lib "eagle-import") (part "RESISTOR0603-RES"))
    )
    (comp (ref "R53")
      (value "270")
      (footprint "eagle-import:0603-RES")
      (libsource (lib "eagle-import") (part "RESISTOR0603-RES"))
    )
    (comp (ref "R54")
      (value "270")
      (footprint "eagle-import:0603-RES")
      (libsource (lib "eagle-import") (part "RESISTOR0603-RES"))
    )
    (comp (ref "R55")
      (value "270")
      (footprint "eagle-import:0603-RES")
      (libsource (lib "eagle-import") (part "RESISTOR0603-RES"))
    )
    (comp (ref "R56")
      (value "270")
      (footprint "eagle-import:0603-RES")
      (libsource (lib "eagle-import") (part "RESISTOR0603-RES"))
    )
    (comp (ref "R57")
      (value "270")
      (footprint "eagle-import:0603-RES")
      (libsource (lib "eagle-import") (part "RESISTOR0603-RES"))
    )
    (comp (ref "R58")
      (value "270")
      (footprint "eagle-import:0603-RES")
      (libsource (lib "eagle-import") (part "RESISTOR0603-RES"))
    )
    (comp (ref "R59")
      (value "270")
      (footprint "eagle-import:0603-RES")
      (libsource (lib "eagle-import") (part "RESISTOR0603-RES"))
    )
    (comp (ref "R60")
      (value "270")
      (footprint "eagle-import:0603-RES")
      (libsource (lib "eagle-import") (part "RESISTOR0603-RES"))
    )
    (comp (ref "R61")
      (value "270")
      (footprint "eagle-import:0603-RES")
      (libsource (lib "eagle-import") (part "RESISTOR0603-RES"))
    )
    (comp (ref "R62")
      (value "270")
      (footprint "eagle-import:0603-RES")
      (libsource (lib "eagle-import") (part "RESISTOR0603-RES"))
    )
    (comp (ref "R63")
      (value "270")
      (footprint "eagle-import:0603-RES")
      (libsource (lib "eagle-import") (part "RESISTOR0603-RES"))
    )
    (comp (ref "R64")
      (value "270")
      (footprint "eagle-import:0603-RES")
      (libsource (lib "eagle-import") (part "RESISTOR0603-RES"))
    )
    (comp (ref "R65")
      (value "270")
      (footprint "eagle-import:0603-RES")
      (libsource (lib "eagle-import") (part "RESISTOR0603-RES"))
    )
    (comp (ref "SERIAL")
      (value "M04X2")
      (footprint "eagle-import:2X4")
      (libsource (lib "eagle-import") (part "SparkFun_M04X2"))
    )
    (comp (ref "SSW1")
      (value "SMART_SWITCHSMART_SWITCH_8PIN")
      (footprint "eagle-import:SMART_SWITCH")
      (libsource (lib "eagle-import") (part "SMART_SWITCHSMART_SWITCH_8PIN"))
    )
    (comp (ref "SW1")
      (value "EC12E_SWCAR1")
      (footprint "eagle-import:ALPS_EC12E_SW-CAR1")
      (libsource (lib "eagle-import") (part "EC12E_SWCAR1"))
    )
    (comp (ref "U$25")
      (value "GNDPAD6MM")
      (footprint "eagle-import:3.2MMPAD6MM")
      (libsource (lib "eagle-import") (part "GNDPAD6MM"))
    )
    (comp (ref "U$26")
      (value "GNDPAD6MM")
      (footprint "eagle-import:3.2MMPAD6MM")
      (libsource (lib "eagle-import") (part "GNDPAD6MM"))
    )
    (comp (ref "U$27")
      (value "GNDPAD6MM")
      (footprint "eagle-import:3.2MMPAD6MM")
      (libsource (lib "eagle-import") (part "GNDPAD6MM"))
    )
    (comp (ref "U$28")
      (value "GNDPAD6MM")
      (footprint "eagle-import:3.2MMPAD6MM")
      (libsource (lib "eagle-import") (part "GNDPAD6MM"))
    )
    (comp (ref "U$51")
      (value "GNDPAD6MM")
      (footprint "eagle-import:3.2MMPAD6MM")
      (libsource (lib "eagle-import") (part "GNDPAD6MM"))
    )
    (comp (ref "U$94")
      (value "M04X2ZIF-0.5")
      (footprint "eagle-import:ZIP-8-0.5")
      (libsource (lib "eagle-import") (part "M04X2ZIF-0.5"))
    )
  )
  (nets
    (net (code "1") (name "5V") (class "Default")
      (node (ref "B1") (pin "COM") (pinfunction "A_COM") (pintype "bidirectional"))
      (node (ref "B10") (pin "COM") (pinfunction "A_COM") (pintype "bidirectional"))
      (node (ref "B10ALT") (pin "COM") (pinfunction "A_COM") (pintype "bidirectional"))
      (node (ref "B11") (pin "COM") (pinfunction "A_COM") (pintype "bidirectional"))
      (node (ref "B11ALT") (pin "COM") (pinfunction "A_COM") (pintype "bidirectional"))
      (node (ref "B12") (pin "COM") (pinfunction "A_COM") (pintype "bidirectional"))
      (node (ref "B12ALT") (pin "COM") (pinfunction "A_COM") (pintype "bidirectional"))
      (node (ref "B13") (pin "COM") (pinfunction "A_COM") (pintype "bidirectional"))
      (node (ref "B13ALT") (pin "COM") (pinfunction "A_COM") (pintype "bidirectional"))
      (node (ref "B13ALT1") (pin "COM") (pinfunction "A_COM") (pintype "bidirectional"))
      (node (ref "B14") (pin "COM") (pinfunction "A_COM") (pintype "bidirectional"))
      (node (ref "B14ALT") (pin "COM") (pinfunction "A_COM") (pintype "bidirectional"))
      (node (ref "B15") (pin "COM") (pinfunction "A_COM") (pintype "bidirectional"))
      (node (ref "B15ALT") (pin "COM") (pinfunction "A_COM") (pintype "bidirectional"))
      (node (ref "B16") (pin "COM") (pinfunction "A_COM") (pintype "bidirectional"))
      (node (ref "B16ALT") (pin "COM") (pinfunction "A_COM") (pintype "bidirectional"))
      (node (ref "B17") (pin "COM") (pinfunction "A_COM") (pintype "bidirectional"))
      (node (ref "B17ALT") (pin "COM") (pinfunction "A_COM") (pintype "bidirectional"))
      (node (ref "B18") (pin "COM") (pinfunction "A_COM") (pintype "bidirectional"))
      (node (ref "B18ALT") (pin "COM") (pinfunction "A_COM") (pintype "bidirectional"))
      (node (ref "B19") (pin "COM") (pinfunction "A_COM") (pintype "bidirectional"))
      (node (ref "B19ALT") (pin "COM") (pinfunction "A_COM") (pintype "bidirectional"))
      (node (ref "B1ALT") (pin "COM") (pinfunction "A_COM") (pintype "bidirectional"))
      (node (ref "B2") (pin "COM") (pinfunction "A_COM") (pintype "bidirectional"))
      (node (ref "B20") (pin "COM") (pinfunction "A_COM") (pintype "bidirectional"))
      (node (ref "B20ALT") (pin "COM") (pinfunction "A_COM") (pintype "bidirectional"))
      (node (ref "B21") (pin "COM") (pinfunction "A_COM") (pintype "bidirectional"))
      (node (ref "B22") (pin "COM") (pinfunction "A_COM") (pintype "bidirectional"))
      (node (ref "B23") (pin "COM") (pinfunction "A_COM") (pintype "bidirectional"))
      (node (ref "B23ALT") (pin "COM") (pinfunction "A_COM") (pintype "bidirectional"))
      (node (ref "B24") (pin "COM") (pinfunction "A_COM") (pintype "bidirectional"))
      (node (ref "B24ALT") (pin "COM") (pinfunction "A_COM") (pintype "bidirectional"))
      (node (ref "B25") (pin "COM") (pinfunction "A_COM") (pintype "bidirectional"))
      (node (ref "B25ALT") (pin "COM") (pinfunction "A_COM") (pintype "bidirectional"))
      (node (ref "B26") (pin "COM") (pinfunction "A_COM") (pintype "bidirectional"))
      (node (ref "B26ALT") (pin "COM") (pinfunction "A_COM") (pintype "bidirectional"))
      (node (ref "B27") (pin "COM") (pinfunction "A_COM") (pintype "bidirectional"))
      (node (ref "B27ALT") (pin "COM") (pinfunction "A_COM") (pintype "bidirectional"))
      (node (ref "B28") (pin "COM") (pinfunction "A_COM") (pintype "bidirectional"))
      (node (ref "B28ALT") (pin "COM") (pinfunction "A_COM") (pintype "bidirectional"))
      (node (ref "B29") (pin "COM") (pinfunction "A_COM") (pintype "bidirectional"))
      (node (ref "B29ALT") (pin "COM") (pinfunction "A_COM") (pintype "bidirectional"))
      (node (ref "B2ALT") (pin "COM") (pinfunction "A_COM") (pintype "bidirectional"))
      (node (ref "B3") (pin "COM") (pinfunction "A_COM") (pintype "bidirectional"))
      (node (ref "B30") (pin "COM") (pinfunction "A_COM") (pintype "bidirectional"))
      (node (ref "B30ALT") (pin "COM") (pinfunction "A_COM") (pintype "bidirectional"))
      (node (ref "B31") (pin "COM") (pinfunction "A_COM") (pintype "bidirectional"))
      (node (ref "B31ALT") (pin "COM") (pinfunction "A_COM") (pintype "bidirectional"))
      (node (ref "B32") (pin "COM") (pinfunction "A_COM") (pintype "bidirectional"))
      (node (ref "B32ALT") (pin "COM") (pinfunction "A_COM") (pintype "bidirectional"))
      (node (ref "B3ALT") (pin "COM") (pinfunction "A_COM") (pintype "bidirectional"))
      (node (ref "B4") (pin "COM") (pinfunction "A_COM") (pintype "bidirectional"))
      (node (ref "B4ALT") (pin "COM") (pinfunction "A_COM") (pintype "bidirectional"))
      (node (ref "B5") (pin "COM") (pinfunction "A_COM") (pintype "bidirectional"))
      (node (ref "B5ALT") (pin "COM") (pinfunction "A_COM") (pintype "bidirectional"))
      (node (ref "B5ALT1") (pin "COM") (pinfunction "A_COM") (pintype "bidirectional"))
      (node (ref "B6") (pin "COM") (pinfunction "A_COM") (pintype "bidirectional"))
      (node (ref "B6ALT") (pin "COM") (pinfunction "A_COM") (pintype "bidirectional"))
      (node (ref "B6ALT1") (pin "COM") (pinfunction "A_COM") (pintype "bidirectional"))
      (node (ref "B7") (pin "COM") (pinfunction "A_COM") (pintype "bidirectional"))
      (node (ref "B7ALT") (pin "COM") (pinfunction "A_COM") (pintype "bidirectional"))
      (node (ref "B7ALT1") (pin "COM") (pinfunction "A_COM") (pintype "bidirectional"))
      (node (ref "B8") (pin "COM") (pinfunction "A_COM") (pintype "bidirectional"))
      (node (ref "B8ALT") (pin "COM") (pinfunction "A_COM") (pintype "bidirectional"))
      (node (ref "B9") (pin "COM") (pinfunction "A_COM") (pintype "bidirectional"))
      (node (ref "B9ALT") (pin "COM") (pinfunction "A_COM") (pintype "bidirectional"))
      (node (ref "B9ALT2") (pin "COM") (pinfunction "A_COM") (pintype "bidirectional"))
      (node (ref "C1") (pin "2") (pinfunction "2_2") (pintype "passive"))
      (node (ref "C13") (pin "2") (pinfunction "2_2") (pintype "passive"))
      (node (ref "C14") (pin "1") (pinfunction "1_1") (pintype "passive"))
      (node (ref "C15") (pin "1") (pinfunction "1_1") (pintype "passive"))
      (node (ref "C16") (pin "1") (pinfunction "1_1") (pintype "passive"))
      (node (ref "C17") (pin "1") (pinfunction "1_1") (pintype "passive"))
      (node (ref "C18") (pin "1") (pinfunction "1_1") (pintype "passive"))
      (node (ref "C19") (pin "1") (pinfunction "1_1") (pintype "passive"))
      (node (ref "C2") (pin "1") (pinfunction "1_1") (pintype "passive"))
      (node (ref "C22") (pin "1") (pinfunction "1_1") (pintype "passive"))
      (node (ref "C3") (pin "2") (pinfunction "2_2") (pintype "passive"))
      (node (ref "C4") (pin "1") (pinfunction "1_1") (pintype "passive"))
      (node (ref "C5") (pin "1") (pinfunction "1_1") (pintype "passive"))
      (node (ref "C6") (pin "1") (pinfunction "1_1") (pintype "passive"))
      (node (ref "C7") (pin "1") (pinfunction "1_1") (pintype "passive"))
      (node (ref "C8") (pin "1") (pinfunction "1_1") (pintype "passive"))
      (node (ref "C9") (pin "2") (pinfunction "2_2") (pintype "passive"))
      (node (ref "IC1") (pin "15") (pinfunction "A0_15") (pintype "input"))
      (node (ref "IC1") (pin "18") (pinfunction "~{RESET}_18") (pintype "input"))
      (node (ref "IC1") (pin "9") (pinfunction "VDD_9") (pintype "power_in"))
      (node (ref "IC2") (pin "1") (pinfunction "A0_1") (pintype "input"))
      (node (ref "IC2") (pin "24") (pinfunction "A5_24") (pintype "input"))
      (node (ref "IC2") (pin "28") (pinfunction "VDD_28") (pintype "power_in"))
      (node (ref "IC2") (pin "4") (pinfunction "A3_4") (pintype "input"))
      (node (ref "IC2") (pin "5") (pinfunction "A4_5") (pintype "input"))
      (node (ref "IC3") (pin "1") (pinfunction "A0_1") (pintype "input"))
      (node (ref "IC3") (pin "24") (pinfunction "A5_24") (pintype "input"))
      (node (ref "IC3") (pin "28") (pinfunction "VDD_28") (pintype "power_in"))
      (node (ref "IC4") (pin "18") (pinfunction "~{RESET}_18") (pintype "input"))
      (node (ref "IC4") (pin "9") (pinfunction "VDD_9") (pintype "power_in"))
      (node (ref "IC5") (pin "14") (pinfunction "VCC_14") (pintype "power_in"))
      (node (ref "IC6") (pin "2") (pinfunction "A1_2") (pintype "input"))
      (node (ref "IC6") (pin "24") (pinfunction "A5_24") (pintype "input"))
      (node (ref "IC6") (pin "28") (pinfunction "VDD_28") (pintype "power_in"))
      (node (ref "IC6") (pin "4") (pinfunction "A3_4") (pintype "input"))
      (node (ref "IC6") (pin "5") (pinfunction "A4_5") (pintype "input"))
      (node (ref "IC7") (pin "16") (pinfunction "A1_16") (pintype "input"))
      (node (ref "IC7") (pin "18") (pinfunction "~{RESET}_18") (pintype "input"))
      (node (ref "IC7") (pin "9") (pinfunction "VDD_9") (pintype "power_in"))
      (node (ref "IC8") (pin "2") (pinfunction "A1_2") (pintype "input"))
      (node (ref "IC8") (pin "24") (pinfunction "A5_24") (pintype "input"))
      (node (ref "IC8") (pin "28") (pinfunction "VDD_28") (pintype "power_in"))
      (node (ref "PC1") (pin "+") (pinfunction "+_+") (pintype "passive"))
      (node (ref "PC2") (pin "+") (pinfunction "+_+") (pintype "passive"))
      (node (ref "POT1") (pin "1") (pinfunction "E_1") (pintype "passive"))
      (node (ref "POT1ALT") (pin "1") (pinfunction "E_1") (pintype "passive"))
      (node (ref "R33") (pin "2") (pinfunction "2_2") (pintype "passive"))
      (node (ref "SERIAL") (pin "2") (pinfunction "2_2") (pintype "passive"))
      (node (ref "SSW1") (pin "4") (pinfunction "VDD_4") (pintype "bidirectional"))
      (node (ref "U$94") (pin "P$2") (pinfunction "2_P$2") (pintype "passive"))
    )
    (net (code "2") (name "A0") (class "Default")
      (node (ref "POT1") (pin "2A") (pinfunction "S_2A") (pintype "passive"))
      (node (ref "POT1ALT") (pin "2A") (pinfunction "S_2A") (pintype "passive"))
      (node (ref "SERIAL") (pin "5") (pinfunction "5_5") (pintype "passive"))
    )
    (net (code "3") (name "AD0") (class "Default")
      (node (ref "C12") (pin "1") (pinfunction "1_1") (pintype "passive"))
      (node (ref "IC4") (pin "1") (pinfunction "GPB0_1") (pintype "bidirectional"))
      (node (ref "SW1") (pin "E") (pinfunction "2_E") (pintype "passive"))
    )
    (net (code "4") (name "D2") (class "Default")
      (node (ref "IC4") (pin "21") (pinfunction "GPA0_21") (pintype "bidirectional"))
      (node (ref "IC5") (pin "12") (pinfunction "O_12") (pintype "output"))
    )
    (net (code "5") (name "D3") (class "Default")
      (node (ref "C11") (pin "1") (pinfunction "1_1") (pintype "passive"))
      (node (ref "IC4") (pin "22") (pinfunction "GPA1_22") (pintype "bidirectional"))
      (node (ref "SW1") (pin "A") (pinfunction "A_A") (pintype "passive"))
    )
    (net (code "6") (name "GND") (class "Default")
      (node (ref "B1") (pin "P$4") (pinfunction "SW1_P$4") (pintype "bidirectional"))
      (node (ref "B10") (pin "P$4") (pinfunction "SW1_P$4") (pintype "bidirectional"))
      (node (ref "B10ALT") (pin "P$4") (pinfunction "SW1_P$4") (pintype "bidirectional"))
      (node (ref "B11") (pin "P$4") (pinfunction "SW1_P$4") (pintype "bidirectional"))
      (node (ref "B11ALT") (pin "P$4") (pinfunction "SW1_P$4") (pintype "bidirectional"))
      (node (ref "B12") (pin "P$4") (pinfunction "SW1_P$4") (pintype "bidirectional"))
      (node (ref "B12ALT") (pin "P$4") (pinfunction "SW1_P$4") (pintype "bidirectional"))
      (node (ref "B13") (pin "P$4") (pinfunction "SW1_P$4") (pintype "bidirectional"))
      (node (ref "B13ALT") (pin "P$4") (pinfunction "SW1_P$4") (pintype "bidirectional"))
      (node (ref "B13ALT1") (pin "P$4") (pinfunction "SW1_P$4") (pintype "bidirectional"))
      (node (ref "B14") (pin "P$4") (pinfunction "SW1_P$4") (pintype "bidirectional"))
      (node (ref "B14ALT") (pin "P$4") (pinfunction "SW1_P$4") (pintype "bidirectional"))
      (node (ref "B15") (pin "P$4") (pinfunction "SW1_P$4") (pintype "bidirectional"))
      (node (ref "B15ALT") (pin "P$4") (pinfunction "SW1_P$4") (pintype "bidirectional"))
      (node (ref "B16") (pin "P$4") (pinfunction "SW1_P$4") (pintype "bidirectional"))
      (node (ref "B16ALT") (pin "P$4") (pinfunction "SW1_P$4") (pintype "bidirectional"))
      (node (ref "B17") (pin "P$4") (pinfunction "SW1_P$4") (pintype "bidirectional"))
      (node (ref "B17ALT") (pin "P$4") (pinfunction "SW1_P$4") (pintype "bidirectional"))
      (node (ref "B18") (pin "P$4") (pinfunction "SW1_P$4") (pintype "bidirectional"))
      (node (ref "B18ALT") (pin "P$4") (pinfunction "SW1_P$4") (pintype "bidirectional"))
      (node (ref "B19") (pin "P$4") (pinfunction "SW1_P$4") (pintype "bidirectional"))
      (node (ref "B19ALT") (pin "P$4") (pinfunction "SW1_P$4") (pintype "bidirectional"))
      (node (ref "B1ALT") (pin "P$4") (pinfunction "SW1_P$4") (pintype "bidirectional"))
      (node (ref "B2") (pin "P$4") (pinfunction "SW1_P$4") (pintype "bidirectional"))
      (node (ref "B20") (pin "P$4") (pinfunction "SW1_P$4") (pintype "bidirectional"))
      (node (ref "B20ALT") (pin "P$4") (pinfunction "SW1_P$4") (pintype "bidirectional"))
      (node (ref "B21") (pin "P$4") (pinfunction "SW1_P$4") (pintype "bidirectional"))
      (node (ref "B22") (pin "P$4") (pinfunction "SW1_P$4") (pintype "bidirectional"))
      (node (ref "B23") (pin "P$4") (pinfunction "SW1_P$4") (pintype "bidirectional"))
      (node (ref "B23ALT") (pin "P$4") (pinfunction "SW1_P$4") (pintype "bidirectional"))
      (node (ref "B24") (pin "P$4") (pinfunction "SW1_P$4") (pintype "bidirectional"))
      (node (ref "B24ALT") (pin "P$4") (pinfunction "SW1_P$4") (pintype "bidirectional"))
      (node (ref "B25") (pin "P$4") (pinfunction "SW1_P$4") (pintype "bidirectional"))
      (node (ref "B25ALT") (pin "P$4") (pinfunction "SW1_P$4") (pintype "bidirectional"))
      (node (ref "B26") (pin "P$4") (pinfunction "SW1_P$4") (pintype "bidirectional"))
      (node (ref "B26ALT") (pin "P$4") (pinfunction "SW1_P$4") (pintype "bidirectional"))
      (node (ref "B27") (pin "P$4") (pinfunction "SW1_P$4") (pintype "bidirectional"))
      (node (ref "B27ALT") (pin "P$4") (pinfunction "SW1_P$4") (pintype "bidirectional"))
      (node (ref "B28") (pin "P$4") (pinfunction "SW1_P$4") (pintype "bidirectional"))
      (node (ref "B28ALT") (pin "P$4") (pinfunction "SW1_P$4") (pintype "bidirectional"))
      (node (ref "B29") (pin "P$4") (pinfunction "SW1_P$4") (pintype "bidirectional"))
      (node (ref "B29ALT") (pin "P$4") (pinfunction "SW1_P$4") (pintype "bidirectional"))
      (node (ref "B2ALT") (pin "P$4") (pinfunction "SW1_P$4") (pintype "bidirectional"))
      (node (ref "B3") (pin "P$4") (pinfunction "SW1_P$4") (pintype "bidirectional"))
      (node (ref "B30") (pin "P$4") (pinfunction "SW1_P$4") (pintype "bidirectional"))
      (node (ref "B30ALT") (pin "P$4") (pinfunction "SW1_P$4") (pintype "bidirectional"))
      (node (ref "B31") (pin "P$4") (pinfunction "SW1_P$4") (pintype "bidirectional"))
      (node (ref "B31ALT") (pin "P$4") (pinfunction "SW1_P$4") (pintype "bidirectional"))
      (node (ref "B32") (pin "P$4") (pinfunction "SW1_P$4") (pintype "bidirectional"))
      (node (ref "B32ALT") (pin "P$4") (pinfunction "SW1_P$4") (pintype "bidirectional"))
      (node (ref "B3ALT") (pin "P$4") (pinfunction "SW1_P$4") (pintype "bidirectional"))
      (node (ref "B4") (pin "P$4") (pinfunction "SW1_P$4") (pintype "bidirectional"))
      (node (ref "B4ALT") (pin "P$4") (pinfunction "SW1_P$4") (pintype "bidirectional"))
      (node (ref "B5") (pin "P$4") (pinfunction "SW1_P$4") (pintype "bidirectional"))
      (node (ref "B5ALT") (pin "P$4") (pinfunction "SW1_P$4") (pintype "bidirectional"))
      (node (ref "B5ALT1") (pin "P$4") (pinfunction "SW1_P$4") (pintype "bidirectional"))
      (node (ref "B6") (pin "P$4") (pinfunction "SW1_P$4") (pintype "bidirectional"))
      (node (ref "B6ALT") (pin "P$4") (pinfunction "SW1_P$4") (pintype "bidirectional"))
      (node (ref "B6ALT1") (pin "P$4") (pinfunction "SW1_P$4") (pintype "bidirectional"))
      (node (ref "B7") (pin "P$4") (pinfunction "SW1_P$4") (pintype "bidirectional"))
      (node (ref "B7ALT") (pin "P$4") (pinfunction "SW1_P$4") (pintype "bidirectional"))
      (node (ref "B7ALT1") (pin "P$4") (pinfunction "SW1_P$4") (pintype "bidirectional"))
      (node (ref "B8") (pin "P$4") (pinfunction "SW1_P$4") (pintype "bidirectional"))
      (node (ref "B8ALT") (pin "P$4") (pinfunction "SW1_P$4") (pintype "bidirectional"))
      (node (ref "B9") (pin "P$4") (pinfunction "SW1_P$4") (pintype "bidirectional"))
      (node (ref "B9ALT") (pin "P$4") (pinfunction "SW1_P$4") (pintype "bidirectional"))
      (node (ref "B9ALT2") (pin "P$4") (pinfunction "SW1_P$4") (pintype "bidirectional"))
      (node (ref "C1") (pin "1") (pinfunction "1_1") (pintype "passive"))
      (node (ref "C10") (pin "2") (pinfunction "2_2") (pintype "passive"))
      (node (ref "C11") (pin "2") (pinfunction "2_2") (pintype "passive"))
      (node (ref "C12") (pin "2") (pinfunction "2_2") (pintype "passive"))
      (node (ref "C13") (pin "1") (pinfunction "1_1") (pintype "passive"))
      (node (ref "C14") (pin "2") (pinfunction "2_2") (pintype "passive"))
      (node (ref "C15") (pin "2") (pinfunction "2_2") (pintype "passive"))
      (node (ref "C16") (pin "2") (pinfunction "2_2") (pintype "passive"))
      (node (ref "C17") (pin "2") (pinfunction "2_2") (pintype "passive"))
      (node (ref "C18") (pin "2") (pinfunction "2_2") (pintype "passive"))
      (node (ref "C19") (pin "2") (pinfunction "2_2") (pintype "passive"))
      (node (ref "C2") (pin "2") (pinfunction "2_2") (pintype "passive"))
      (node (ref "C22") (pin "2") (pinfunction "2_2") (pintype "passive"))
      (node (ref "C3") (pin "1") (pinfunction "1_1") (pintype "passive"))
      (node (ref "C4") (pin "2") (pinfunction "2_2") (pintype "passive"))
      (node (ref "C5") (pin "2") (pinfunction "2_2") (pintype "passive"))
      (node (ref "C6") (pin "2") (pinfunction "2_2") (pintype "passive"))
      (node (ref "C7") (pin "2") (pinfunction "2_2") (pintype "passive"))
      (node (ref "C8") (pin "2") (pinfunction "2_2") (pintype "passive"))
      (node (ref "C9") (pin "1") (pinfunction "1_1") (pintype "passive"))
      (node (ref "IC1") (pin "10") (pinfunction "VSS_10") (pintype "power_in"))
      (node (ref "IC1") (pin "16") (pinfunction "A1_16") (pintype "input"))
      (node (ref "IC1") (pin "17") (pinfunction "A2_17") (pintype "input"))
      (node (ref "IC2") (pin "14") (pinfunction "GND_14") (pintype "power_in"))
      (node (ref "IC2") (pin "2") (pinfunction "A1_2") (pintype "input"))
      (node (ref "IC2") (pin "23") (pinfunction "OE_23") (pintype "input"))
      (node (ref "IC2") (pin "25") (pinfunction "EXTCLK_25") (pintype "input"))
      (node (ref "IC2") (pin "3") (pinfunction "A2_3") (pintype "input"))
      (node (ref "IC3") (pin "14") (pinfunction "GND_14") (pintype "power_in"))
      (node (ref "IC3") (pin "2") (pinfunction "A1_2") (pintype "input"))
      (node (ref "IC3") (pin "23") (pinfunction "OE_23") (pintype "input"))
      (node (ref "IC3") (pin "25") (pinfunction "EXTCLK_25") (pintype "input"))
      (node (ref "IC3") (pin "3") (pinfunction "A2_3") (pintype "input"))
      (node (ref "IC3") (pin "4") (pinfunction "A3_4") (pintype "input"))
      (node (ref "IC3") (pin "5") (pinfunction "A4_5") (pintype "input"))
      (node (ref "IC4") (pin "10") (pinfunction "VSS_10") (pintype "power_in"))
      (node (ref "IC4") (pin "15") (pinfunction "A0_15") (pintype "input"))
      (node (ref "IC4") (pin "16") (pinfunction "A1_16") (pintype "input"))
      (node (ref "IC4") (pin "17") (pinfunction "A2_17") (pintype "input"))
      (node (ref "IC5") (pin "1") (pinfunction "I_1") (pintype "input"))
      (node (ref "IC5") (pin "11") (pinfunction "I_11") (pintype "input"))
      (node (ref "IC5") (pin "3") (pinfunction "I_3") (pintype "input"))
      (node (ref "IC5") (pin "5") (pinfunction "I_5") (pintype "input"))
      (node (ref "IC5") (pin "7") (pinfunction "GND_7") (pintype "power_in"))
      (node (ref "IC5") (pin "9") (pinfunction "I_9") (pintype "input"))
      (node (ref "IC6") (pin "1") (pinfunction "A0_1") (pintype "input"))
      (node (ref "IC6") (pin "14") (pinfunction "GND_14") (pintype "power_in"))
      (node (ref "IC6") (pin "23") (pinfunction "OE_23") (pintype "input"))
      (node (ref "IC6") (pin "25") (pinfunction "EXTCLK_25") (pintype "input"))
      (node (ref "IC6") (pin "3") (pinfunction "A2_3") (pintype "input"))
      (node (ref "IC7") (pin "10") (pinfunction "VSS_10") (pintype "power_in"))
      (node (ref "IC7") (pin "15") (pinfunction "A0_15") (pintype "input"))
      (node (ref "IC7") (pin "17") (pinfunction "A2_17") (pintype "input"))
      (node (ref "IC8") (pin "1") (pinfunction "A0_1") (pintype "input"))
      (node (ref "IC8") (pin "14") (pinfunction "GND_14") (pintype "power_in"))
      (node (ref "IC8") (pin "23") (pinfunction "OE_23") (pintype "input"))
      (node (ref "IC8") (pin "25") (pinfunction "EXTCLK_25") (pintype "input"))
      (node (ref "IC8") (pin "3") (pinfunction "A2_3") (pintype "input"))
      (node (ref "IC8") (pin "4") (pinfunction "A3_4") (pintype "input"))
      (node (ref "IC8") (pin "5") (pinfunction "A4_5") (pintype "input"))
      (node (ref "PC1") (pin "-") (pinfunction "-_-") (pintype "passive"))
      (node (ref "PC2") (pin "-") (pinfunction "-_-") (pintype "passive"))
      (node (ref "POT1") (pin "3") (pinfunction "A_3") (pintype "passive"))
      (node (ref "POT1ALT") (pin "3") (pinfunction "A_3") (pintype "passive"))
      (node (ref "SERIAL") (pin "1") (pinfunction "1_1") (pintype "passive"))
      (node (ref "SSW1") (pin "1") (pinfunction "SW1_1") (pintype "bidirectional"))
      (node (ref "SSW1") (pin "3") (pinfunction "GND_3") (pintype "bidirectional"))
      (node (ref "SW1") (pin "C") (pinfunction "C_C") (pintype "passive"))
      (node (ref "SW1") (pin "D") (pinfunction "1_D") (pintype "passive"))
      (node (ref "U$25") (pin "P$1") (pinfunction "1_P$1") (pintype "passive"))
      (node (ref "U$26") (pin "P$1") (pinfunction "1_P$1") (pintype "passive"))
      (node (ref "U$27") (pin "P$1") (pinfunction "1_P$1") (pintype "passive"))
      (node (ref "U$28") (pin "P$1") (pinfunction "1_P$1") (pintype "passive"))
      (node (ref "U$51") (pin "P$1") (pinfunction "1_P$1") (pintype "passive"))
      (node (ref "U$94") (pin "P$1") (pinfunction "1_P$1") (pintype "passive"))
    )
    (net (code "7") (name "GPA0") (class "Default")
      (node (ref "B8") (pin "P$5") (pinfunction "SW2_P$5") (pintype "bidirectional"))
      (node (ref "B8ALT") (pin "P$5") (pinfunction "SW2_P$5") (pintype "bidirectional"))
      (node (ref "IC1") (pin "21") (pinfunction "GPA0_21") (pintype "bidirectional"))
    )
    (net (code "8") (name "GPA1") (class "Default")
      (node (ref "B7") (pin "P$5") (pinfunction "SW2_P$5") (pintype "bidirectional"))
      (node (ref "B7ALT") (pin "P$5") (pinfunction "SW2_P$5") (pintype "bidirectional"))
      (node (ref "B7ALT1") (pin "P$5") (pinfunction "SW2_P$5") (pintype "bidirectional"))
      (node (ref "IC1") (pin "22") (pinfunction "GPA1_22") (pintype "bidirectional"))
    )
    (net (code "9") (name "GPA2") (class "Default")
      (node (ref "B6") (pin "P$5") (pinfunction "SW2_P$5") (pintype "bidirectional"))
      (node (ref "B6ALT") (pin "P$5") (pinfunction "SW2_P$5") (pintype "bidirectional"))
      (node (ref "B6ALT1") (pin "P$5") (pinfunction "SW2_P$5") (pintype "bidirectional"))
      (node (ref "IC1") (pin "23") (pinfunction "GPA2_23") (pintype "bidirectional"))
    )
    (net (code "10") (name "GPA3") (class "Default")
      (node (ref "B5") (pin "P$5") (pinfunction "SW2_P$5") (pintype "bidirectional"))
      (node (ref "B5ALT") (pin "P$5") (pinfunction "SW2_P$5") (pintype "bidirectional"))
      (node (ref "B5ALT1") (pin "P$5") (pinfunction "SW2_P$5") (pintype "bidirectional"))
      (node (ref "IC1") (pin "24") (pinfunction "GPA3_24") (pintype "bidirectional"))
    )
    (net (code "11") (name "GPA4") (class "Default")
      (node (ref "B1") (pin "P$5") (pinfunction "SW2_P$5") (pintype "bidirectional"))
      (node (ref "B1ALT") (pin "P$5") (pinfunction "SW2_P$5") (pintype "bidirectional"))
      (node (ref "IC1") (pin "25") (pinfunction "GPA4_25") (pintype "bidirectional"))
    )
    (net (code "12") (name "GPA4S") (class "Default")
      (node (ref "IC4") (pin "25") (pinfunction "GPA4_25") (pintype "bidirectional"))
      (node (ref "SSW1") (pin "2") (pinfunction "SW2_2") (pintype "bidirectional"))
    )
    (net (code "13") (name "GPA5") (class "Default")
      (node (ref "B2") (pin "P$5") (pinfunction "SW2_P$5") (pintype "bidirectional"))
      (node (ref "B2ALT") (pin "P$5") (pinfunction "SW2_P$5") (pintype "bidirectional"))
      (node (ref "IC1") (pin "26") (pinfunction "GPA5_26") (pintype "bidirectional"))
    )
    (net (code "14") (name "GPA6") (class "Default")
      (node (ref "B3") (pin "P$5") (pinfunction "SW2_P$5") (pintype "bidirectional"))
      (node (ref "B3ALT") (pin "P$5") (pinfunction "SW2_P$5") (pintype "bidirectional"))
      (node (ref "IC1") (pin "27") (pinfunction "GPA6_27") (pintype "bidirectional"))
    )
    (net (code "15") (name "GPA7") (class "Default")
      (node (ref "B4") (pin "P$5") (pinfunction "SW2_P$5") (pintype "bidirectional"))
      (node (ref "B4ALT") (pin "P$5") (pinfunction "SW2_P$5") (pintype "bidirectional"))
      (node (ref "IC1") (pin "28") (pinfunction "GPA7_28") (pintype "bidirectional"))
    )
    (net (code "16") (name "GPA8") (class "Default")
      (node (ref "B16") (pin "P$5") (pinfunction "SW2_P$5") (pintype "bidirectional"))
      (node (ref "B16ALT") (pin "P$5") (pinfunction "SW2_P$5") (pintype "bidirectional"))
      (node (ref "IC1") (pin "1") (pinfunction "GPB0_1") (pintype "bidirectional"))
    )
    (net (code "17") (name "GPA9") (class "Default")
      (node (ref "B15") (pin "P$5") (pinfunction "SW2_P$5") (pintype "bidirectional"))
      (node (ref "B15ALT") (pin "P$5") (pinfunction "SW2_P$5") (pintype "bidirectional"))
      (node (ref "IC1") (pin "2") (pinfunction "GPB1_2") (pintype "bidirectional"))
    )
    (net (code "18") (name "GPA10") (class "Default")
      (node (ref "B14") (pin "P$5") (pinfunction "SW2_P$5") (pintype "bidirectional"))
      (node (ref "B14ALT") (pin "P$5") (pinfunction "SW2_P$5") (pintype "bidirectional"))
      (node (ref "IC1") (pin "3") (pinfunction "GPB2_3") (pintype "bidirectional"))
    )
    (net (code "19") (name "GPA11") (class "Default")
      (node (ref "B13") (pin "P$5") (pinfunction "SW2_P$5") (pintype "bidirectional"))
      (node (ref "B13ALT") (pin "P$5") (pinfunction "SW2_P$5") (pintype "bidirectional"))
      (node (ref "B13ALT1") (pin "P$5") (pinfunction "SW2_P$5") (pintype "bidirectional"))
      (node (ref "IC1") (pin "4") (pinfunction "GPB3_4") (pintype "bidirectional"))
    )
    (net (code "20") (name "GPA12") (class "Default")
      (node (ref "B9") (pin "P$5") (pinfunction "SW2_P$5") (pintype "bidirectional"))
      (node (ref "B9ALT") (pin "P$5") (pinfunction "SW2_P$5") (pintype "bidirectional"))
      (node (ref "B9ALT2") (pin "P$5") (pinfunction "SW2_P$5") (pintype "bidirectional"))
      (node (ref "IC1") (pin "5") (pinfunction "GPB4_5") (pintype "bidirectional"))
    )
    (net (code "21") (name "GPA13") (class "Default")
      (node (ref "B10") (pin "P$5") (pinfunction "SW2_P$5") (pintype "bidirectional"))
      (node (ref "B10ALT") (pin "P$5") (pinfunction "SW2_P$5") (pintype "bidirectional"))
      (node (ref "IC1") (pin "6") (pinfunction "GPB5_6") (pintype "bidirectional"))
    )
    (net (code "22") (name "GPA14") (class "Default")
      (node (ref "B11") (pin "P$5") (pinfunction "SW2_P$5") (pintype "bidirectional"))
      (node (ref "B11ALT") (pin "P$5") (pinfunction "SW2_P$5") (pintype "bidirectional"))
      (node (ref "IC1") (pin "7") (pinfunction "GPB6_7") (pintype "bidirectional"))
    )
    (net (code "23") (name "GPA15") (class "Default")
      (node (ref "B12") (pin "P$5") (pinfunction "SW2_P$5") (pintype "bidirectional"))
      (node (ref "B12ALT") (pin "P$5") (pinfunction "SW2_P$5") (pintype "bidirectional"))
      (node (ref "IC1") (pin "8") (pinfunction "GPB7_8") (pintype "bidirectional"))
    )
    (net (code "24") (name "GPA16") (class "Default")
      (node (ref "B24") (pin "P$5") (pinfunction "SW2_P$5") (pintype "bidirectional"))
      (node (ref "B24ALT") (pin "P$5") (pinfunction "SW2_P$5") (pintype "bidirectional"))
      (node (ref "IC7") (pin "21") (pinfunction "GPA0_21") (pintype "bidirectional"))
    )
    (net (code "25") (name "GPA17") (class "Default")
      (node (ref "B23") (pin "P$5") (pinfunction "SW2_P$5") (pintype "bidirectional"))
      (node (ref "B23ALT") (pin "P$5") (pinfunction "SW2_P$5") (pintype "bidirectional"))
      (node (ref "IC7") (pin "22") (pinfunction "GPA1_22") (pintype "bidirectional"))
    )
    (net (code "26") (name "GPA18") (class "Default")
      (node (ref "B22") (pin "P$5") (pinfunction "SW2_P$5") (pintype "bidirectional"))
      (node (ref "IC7") (pin "23") (pinfunction "GPA2_23") (pintype "bidirectional"))
    )
    (net (code "27") (name "GPA19") (class "Default")
      (node (ref "B21") (pin "P$5") (pinfunction "SW2_P$5") (pintype "bidirectional"))
      (node (ref "IC7") (pin "24") (pinfunction "GPA3_24") (pintype "bidirectional"))
    )
    (net (code "28") (name "GPA20") (class "Default")
      (node (ref "B17") (pin "P$5") (pinfunction "SW2_P$5") (pintype "bidirectional"))
      (node (ref "B17ALT") (pin "P$5") (pinfunction "SW2_P$5") (pintype "bidirectional"))
      (node (ref "IC7") (pin "25") (pinfunction "GPA4_25") (pintype "bidirectional"))
    )
    (net (code "29") (name "GPA21") (class "Default")
      (node (ref "B18") (pin "P$5") (pinfunction "SW2_P$5") (pintype "bidirectional"))
      (node (ref "B18ALT") (pin "P$5") (pinfunction "SW2_P$5") (pintype "bidirectional"))
      (node (ref "IC7") (pin "26") (pinfunction "GPA5_26") (pintype "bidirectional"))
    )
    (net (code "30") (name "GPA22") (class "Default")
      (node (ref "B19") (pin "P$5") (pinfunction "SW2_P$5") (pintype "bidirectional"))
      (node (ref "B19ALT") (pin "P$5") (pinfunction "SW2_P$5") (pintype "bidirectional"))
      (node (ref "IC7") (pin "27") (pinfunction "GPA6_27") (pintype "bidirectional"))
    )
    (net (code "31") (name "GPA23") (class "Default")
      (node (ref "B20") (pin "P$5") (pinfunction "SW2_P$5") (pintype "bidirectional"))
      (node (ref "B20ALT") (pin "P$5") (pinfunction "SW2_P$5") (pintype "bidirectional"))
      (node (ref "IC7") (pin "28") (pinfunction "GPA7_28") (pintype "bidirectional"))
    )
    (net (code "32") (name "GPA24") (class "Default")
      (node (ref "B32") (pin "P$5") (pinfunction "SW2_P$5") (pintype "bidirectional"))
      (node (ref "B32ALT") (pin "P$5") (pinfunction "SW2_P$5") (pintype "bidirectional"))
      (node (ref "IC7") (pin "1") (pinfunction "GPB0_1") (pintype "bidirectional"))
    )
    (net (code "33") (name "GPA25") (class "Default")
      (node (ref "B31") (pin "P$5") (pinfunction "SW2_P$5") (pintype "bidirectional"))
      (node (ref "B31ALT") (pin "P$5") (pinfunction "SW2_P$5") (pintype "bidirectional"))
      (node (ref "IC7") (pin "2") (pinfunction "GPB1_2") (pintype "bidirectional"))
    )
    (net (code "34") (name "GPA26") (class "Default")
      (node (ref "B30") (pin "P$5") (pinfunction "SW2_P$5") (pintype "bidirectional"))
      (node (ref "B30ALT") (pin "P$5") (pinfunction "SW2_P$5") (pintype "bidirectional"))
      (node (ref "IC7") (pin "3") (pinfunction "GPB2_3") (pintype "bidirectional"))
    )
    (net (code "35") (name "GPA27") (class "Default")
      (node (ref "B29") (pin "P$5") (pinfunction "SW2_P$5") (pintype "bidirectional"))
      (node (ref "B29ALT") (pin "P$5") (pinfunction "SW2_P$5") (pintype "bidirectional"))
      (node (ref "IC7") (pin "4") (pinfunction "GPB3_4") (pintype "bidirectional"))
    )
    (net (code "36") (name "GPA28") (class "Default")
      (node (ref "B25") (pin "P$5") (pinfunction "SW2_P$5") (pintype "bidirectional"))
      (node (ref "B25ALT") (pin "P$5") (pinfunction "SW2_P$5") (pintype "bidirectional"))
      (node (ref "IC7") (pin "5") (pinfunction "GPB4_5") (pintype "bidirectional"))
    )
    (net (code "37") (name "GPA29") (class "Default")
      (node (ref "B26") (pin "P$5") (pinfunction "SW2_P$5") (pintype "bidirectional"))
      (node (ref "B26ALT") (pin "P$5") (pinfunction "SW2_P$5") (pintype "bidirectional"))
      (node (ref "IC7") (pin "6") (pinfunction "GPB5_6") (pintype "bidirectional"))
    )
    (net (code "38") (name "GPA30") (class "Default")
      (node (ref "B27") (pin "P$5") (pinfunction "SW2_P$5") (pintype "bidirectional"))
      (node (ref "B27ALT") (pin "P$5") (pinfunction "SW2_P$5") (pintype "bidirectional"))
      (node (ref "IC7") (pin "7") (pinfunction "GPB6_7") (pintype "bidirectional"))
    )
    (net (code "39") (name "GPA31") (class "Default")
      (node (ref "B28") (pin "P$5") (pinfunction "SW2_P$5") (pintype "bidirectional"))
      (node (ref "B28ALT") (pin "P$5") (pinfunction "SW2_P$5") (pintype "bidirectional"))
      (node (ref "IC7") (pin "8") (pinfunction "GPB7_8") (pintype "bidirectional"))
    )
    (net (code "40") (name "GPB4") (class "Default")
      (node (ref "IC4") (pin "5") (pinfunction "GPB4_5") (pintype "bidirectional"))
      (node (ref "SSW1") (pin "8") (pinfunction "SS_8") (pintype "bidirectional"))
    )
    (net (code "41") (name "I2C_SCL") (class "Default")
      (node (ref "IC1") (pin "12") (pinfunction "SCL_12") (pintype "input"))
      (node (ref "IC2") (pin "26") (pinfunction "SCL_26") (pintype "input"))
      (node (ref "IC3") (pin "26") (pinfunction "SCL_26") (pintype "input"))
      (node (ref "IC4") (pin "12") (pinfunction "SCL_12") (pintype "input"))
      (node (ref "IC6") (pin "26") (pinfunction "SCL_26") (pintype "input"))
      (node (ref "IC7") (pin "12") (pinfunction "SCL_12") (pintype "input"))
      (node (ref "IC8") (pin "26") (pinfunction "SCL_26") (pintype "input"))
      (node (ref "SERIAL") (pin "4") (pinfunction "4_4") (pintype "passive"))
      (node (ref "U$94") (pin "P$4") (pinfunction "4_P$4") (pintype "passive"))
    )
    (net (code "42") (name "I2C_SDA") (class "Default")
      (node (ref "IC1") (pin "13") (pinfunction "SDA_13") (pintype "bidirectional"))
      (node (ref "IC2") (pin "27") (pinfunction "SDA_27") (pintype "input"))
      (node (ref "IC3") (pin "27") (pinfunction "SDA_27") (pintype "input"))
      (node (ref "IC4") (pin "13") (pinfunction "SDA_13") (pintype "bidirectional"))
      (node (ref "IC6") (pin "27") (pinfunction "SDA_27") (pintype "input"))
      (node (ref "IC7") (pin "13") (pinfunction "SDA_13") (pintype "bidirectional"))
      (node (ref "IC8") (pin "27") (pinfunction "SDA_27") (pintype "input"))
      (node (ref "SERIAL") (pin "3") (pinfunction "3_3") (pintype "passive"))
      (node (ref "U$94") (pin "P$3") (pinfunction "3_P$3") (pintype "passive"))
    )
    (net (code "43") (name "L0") (class "Default")
      (node (ref "B1") (pin "P$2") (pinfunction "K1_P$2") (pintype "bidirectional"))
      (node (ref "B1ALT") (pin "P$2") (pinfunction "K1_P$2") (pintype "bidirectional"))
      (node (ref "R20") (pin "1") (pinfunction "1_1") (pintype "passive"))
    )
    (net (code "44") (name "L1") (class "Default")
      (node (ref "B1") (pin "P$3") (pinfunction "K2_P$3") (pintype "bidirectional"))
      (node (ref "B1ALT") (pin "P$3") (pinfunction "K2_P$3") (pintype "bidirectional"))
      (node (ref "R19") (pin "1") (pinfunction "1_1") (pintype "passive"))
    )
    (net (code "45") (name "L2") (class "Default")
      (node (ref "B2") (pin "P$2") (pinfunction "K1_P$2") (pintype "bidirectional"))
      (node (ref "B2ALT") (pin "P$2") (pinfunction "K1_P$2") (pintype "bidirectional"))
      (node (ref "R18") (pin "1") (pinfunction "1_1") (pintype "passive"))
    )
    (net (code "46") (name "L3") (class "Default")
      (node (ref "B2") (pin "P$3") (pinfunction "K2_P$3") (pintype "bidirectional"))
      (node (ref "B2ALT") (pin "P$3") (pinfunction "K2_P$3") (pintype "bidirectional"))
      (node (ref "R17") (pin "1") (pinfunction "1_1") (pintype "passive"))
    )
    (net (code "47") (name "L4") (class "Default")
      (node (ref "B3") (pin "P$2") (pinfunction "K1_P$2") (pintype "bidirectional"))
      (node (ref "B3ALT") (pin "P$2") (pinfunction "K1_P$2") (pintype "bidirectional"))
      (node (ref "R16") (pin "1") (pinfunction "1_1") (pintype "passive"))
    )
    (net (code "48") (name "L5") (class "Default")
      (node (ref "B3") (pin "P$3") (pinfunction "K2_P$3") (pintype "bidirectional"))
      (node (ref "B3ALT") (pin "P$3") (pinfunction "K2_P$3") (pintype "bidirectional"))
      (node (ref "R15") (pin "1") (pinfunction "1_1") (pintype "passive"))
    )
    (net (code "49") (name "L6") (class "Default")
      (node (ref "B4") (pin "P$2") (pinfunction "K1_P$2") (pintype "bidirectional"))
      (node (ref "B4ALT") (pin "P$2") (pinfunction "K1_P$2") (pintype "bidirectional"))
      (node (ref "R14") (pin "1") (pinfunction "1_1") (pintype "passive"))
    )
    (net (code "50") (name "L7") (class "Default")
      (node (ref "B4") (pin "P$3") (pinfunction "K2_P$3") (pintype "bidirectional"))
      (node (ref "B4ALT") (pin "P$3") (pinfunction "K2_P$3") (pintype "bidirectional"))
      (node (ref "R13") (pin "1") (pinfunction "1_1") (pintype "passive"))
    )
    (net (code "51") (name "L8") (class "Default")
      (node (ref "B5") (pin "P$2") (pinfunction "K1_P$2") (pintype "bidirectional"))
      (node (ref "B5ALT") (pin "P$2") (pinfunction "K1_P$2") (pintype "bidirectional"))
      (node (ref "B5ALT1") (pin "P$2") (pinfunction "K1_P$2") (pintype "bidirectional"))
      (node (ref "R12") (pin "1") (pinfunction "1_1") (pintype "passive"))
    )
    (net (code "52") (name "L9") (class "Default")
      (node (ref "B5") (pin "P$3") (pinfunction "K2_P$3") (pintype "bidirectional"))
      (node (ref "B5ALT") (pin "P$3") (pinfunction "K2_P$3") (pintype "bidirectional"))
      (node (ref "B5ALT1") (pin "P$3") (pinfunction "K2_P$3") (pintype "bidirectional"))
      (node (ref "R11") (pin "1") (pinfunction "1_1") (pintype "passive"))
    )
    (net (code "53") (name "L10") (class "Default")
      (node (ref "B6") (pin "P$2") (pinfunction "K1_P$2") (pintype "bidirectional"))
      (node (ref "B6ALT") (pin "P$2") (pinfunction "K1_P$2") (pintype "bidirectional"))
      (node (ref "B6ALT1") (pin "P$2") (pinfunction "K1_P$2") (pintype "bidirectional"))
      (node (ref "R10") (pin "1") (pinfunction "1_1") (pintype "passive"))
    )
    (net (code "54") (name "L11") (class "Default")
      (node (ref "B6") (pin "P$3") (pinfunction "K2_P$3") (pintype "bidirectional"))
      (node (ref "B6ALT") (pin "P$3") (pinfunction "K2_P$3") (pintype "bidirectional"))
      (node (ref "B6ALT1") (pin "P$3") (pinfunction "K2_P$3") (pintype "bidirectional"))
      (node (ref "R9") (pin "1") (pinfunction "1_1") (pintype "passive"))
    )
    (net (code "55") (name "L12") (class "Default")
      (node (ref "B7") (pin "P$2") (pinfunction "K1_P$2") (pintype "bidirectional"))
      (node (ref "B7ALT") (pin "P$2") (pinfunction "K1_P$2") (pintype "bidirectional"))
      (node (ref "B7ALT1") (pin "P$2") (pinfunction "K1_P$2") (pintype "bidirectional"))
      (node (ref "R8") (pin "1") (pinfunction "1_1") (pintype "passive"))
    )
    (net (code "56") (name "L13") (class "Default")
      (node (ref "B7") (pin "P$3") (pinfunction "K2_P$3") (pintype "bidirectional"))
      (node (ref "B7ALT") (pin "P$3") (pinfunction "K2_P$3") (pintype "bidirectional"))
      (node (ref "B7ALT1") (pin "P$3") (pinfunction "K2_P$3") (pintype "bidirectional"))
      (node (ref "R7") (pin "1") (pinfunction "1_1") (pintype "passive"))
    )
    (net (code "57") (name "L14") (class "Default")
      (node (ref "B8") (pin "P$2") (pinfunction "K1_P$2") (pintype "bidirectional"))
      (node (ref "B8ALT") (pin "P$2") (pinfunction "K1_P$2") (pintype "bidirectional"))
      (node (ref "R6") (pin "1") (pinfunction "1_1") (pintype "passive"))
    )
    (net (code "58") (name "L15") (class "Default")
      (node (ref "B8") (pin "P$3") (pinfunction "K2_P$3") (pintype "bidirectional"))
      (node (ref "B8ALT") (pin "P$3") (pinfunction "K2_P$3") (pintype "bidirectional"))
      (node (ref "R5") (pin "1") (pinfunction "1_1") (pintype "passive"))
    )
    (net (code "59") (name "L16") (class "Default")
      (node (ref "B9") (pin "P$2") (pinfunction "K1_P$2") (pintype "bidirectional"))
      (node (ref "B9ALT") (pin "P$2") (pinfunction "K1_P$2") (pintype "bidirectional"))
      (node (ref "B9ALT2") (pin "P$2") (pinfunction "K1_P$2") (pintype "bidirectional"))
      (node (ref "R32") (pin "1") (pinfunction "1_1") (pintype "passive"))
    )
    (net (code "60") (name "L17") (class "Default")
      (node (ref "B9") (pin "P$3") (pinfunction "K2_P$3") (pintype "bidirectional"))
      (node (ref "B9ALT") (pin "P$3") (pinfunction "K2_P$3") (pintype "bidirectional"))
      (node (ref "B9ALT2") (pin "P$3") (pinfunction "K2_P$3") (pintype "bidirectional"))
      (node (ref "R31") (pin "1") (pinfunction "1_1") (pintype "passive"))
    )
    (net (code "61") (name "L18") (class "Default")
      (node (ref "B10") (pin "P$2") (pinfunction "K1_P$2") (pintype "bidirectional"))
      (node (ref "B10ALT") (pin "P$2") (pinfunction "K1_P$2") (pintype "bidirectional"))
      (node (ref "R30") (pin "1") (pinfunction "1_1") (pintype "passive"))
    )
    (net (code "62") (name "L19") (class "Default")
      (node (ref "B10") (pin "P$3") (pinfunction "K2_P$3") (pintype "bidirectional"))
      (node (ref "B10ALT") (pin "P$3") (pinfunction "K2_P$3") (pintype "bidirectional"))
      (node (ref "R29") (pin "1") (pinfunction "1_1") (pintype "passive"))
    )
    (net (code "63") (name "L20") (class "Default")
      (node (ref "B11") (pin "P$2") (pinfunction "K1_P$2") (pintype "bidirectional"))
      (node (ref "B11ALT") (pin "P$2") (pinfunction "K1_P$2") (pintype "bidirectional"))
      (node (ref "R28") (pin "1") (pinfunction "1_1") (pintype "passive"))
    )
    (net (code "64") (name "L21") (class "Default")
      (node (ref "B11") (pin "P$3") (pinfunction "K2_P$3") (pintype "bidirectional"))
      (node (ref "B11ALT") (pin "P$3") (pinfunction "K2_P$3") (pintype "bidirectional"))
      (node (ref "R27") (pin "1") (pinfunction "1_1") (pintype "passive"))
    )
    (net (code "65") (name "L22") (class "Default")
      (node (ref "B12") (pin "P$2") (pinfunction "K1_P$2") (pintype "bidirectional"))
      (node (ref "B12ALT") (pin "P$2") (pinfunction "K1_P$2") (pintype "bidirectional"))
      (node (ref "R57") (pin "1") (pinfunction "1_1") (pintype "passive"))
    )
    (net (code "66") (name "L23") (class "Default")
      (node (ref "B12") (pin "P$3") (pinfunction "K2_P$3") (pintype "bidirectional"))
      (node (ref "B12ALT") (pin "P$3") (pinfunction "K2_P$3") (pintype "bidirectional"))
      (node (ref "R56") (pin "1") (pinfunction "1_1") (pintype "passive"))
    )
    (net (code "67") (name "L24") (class "Default")
      (node (ref "B13") (pin "P$2") (pinfunction "K1_P$2") (pintype "bidirectional"))
      (node (ref "B13ALT") (pin "P$2") (pinfunction "K1_P$2") (pintype "bidirectional"))
      (node (ref "B13ALT1") (pin "P$2") (pinfunction "K1_P$2") (pintype "bidirectional"))
      (node (ref "R63") (pin "1") (pinfunction "1_1") (pintype "passive"))
    )
    (net (code "68") (name "L25") (class "Default")
      (node (ref "B13") (pin "P$3") (pinfunction "K2_P$3") (pintype "bidirectional"))
      (node (ref "B13ALT") (pin "P$3") (pinfunction "K2_P$3") (pintype "bidirectional"))
      (node (ref "B13ALT1") (pin "P$3") (pinfunction "K2_P$3") (pintype "bidirectional"))
      (node (ref "R62") (pin "1") (pinfunction "1_1") (pintype "passive"))
    )
    (net (code "69") (name "L26") (class "Default")
      (node (ref "B14") (pin "P$2") (pinfunction "K1_P$2") (pintype "bidirectional"))
      (node (ref "B14ALT") (pin "P$2") (pinfunction "K1_P$2") (pintype "bidirectional"))
      (node (ref "R61") (pin "1") (pinfunction "1_1") (pintype "passive"))
    )
    (net (code "70") (name "L27") (class "Default")
      (node (ref "B14") (pin "P$3") (pinfunction "K2_P$3") (pintype "bidirectional"))
      (node (ref "B14ALT") (pin "P$3") (pinfunction "K2_P$3") (pintype "bidirectional"))
      (node (ref "R60") (pin "1") (pinfunction "1_1") (pintype "passive"))
    )
    (net (code "71") (name "L28") (class "Default")
      (node (ref "B15") (pin "P$2") (pinfunction "K1_P$2") (pintype "bidirectional"))
      (node (ref "B15ALT") (pin "P$2") (pinfunction "K1_P$2") (pintype "bidirectional"))
      (node (ref "R59") (pin "1") (pinfunction "1_1") (pintype "passive"))
    )
    (net (code "72") (name "L29") (class "Default")
      (node (ref "B15") (pin "P$3") (pinfunction "K2_P$3") (pintype "bidirectional"))
      (node (ref "B15ALT") (pin "P$3") (pinfunction "K2_P$3") (pintype "bidirectional"))
      (node (ref "R58") (pin "1") (pinfunction "1_1") (pintype "passive"))
    )
    (net (code "73") (name "L30") (class "Default")
      (node (ref "B16") (pin "P$2") (pinfunction "K1_P$2") (pintype "bidirectional"))
      (node (ref "B16ALT") (pin "P$2") (pinfunction "K1_P$2") (pintype "bidirectional"))
      (node (ref "R65") (pin "1") (pinfunction "1_1") (pintype "passive"))
    )
    (net (code "74") (name "L31") (class "Default")
      (node (ref "B16") (pin "P$3") (pinfunction "K2_P$3") (pintype "bidirectional"))
      (node (ref "B16ALT") (pin "P$3") (pinfunction "K2_P$3") (pintype "bidirectional"))
      (node (ref "R64") (pin "1") (pinfunction "1_1") (pintype "passive"))
    )
    (net (code "75") (name "L32") (class "Default")
      (node (ref "B17") (pin "P$2") (pinfunction "K1_P$2") (pintype "bidirectional"))
      (node (ref "B17ALT") (pin "P$2") (pinfunction "K1_P$2") (pintype "bidirectional"))
      (node (ref "R39") (pin "1") (pinfunction "1_1") (pintype "passive"))
    )
    (net (code "76") (name "L33") (class "Default")
      (node (ref "B17") (pin "P$3") (pinfunction "K2_P$3") (pintype "bidirectional"))
      (node (ref "B17ALT") (pin "P$3") (pinfunction "K2_P$3") (pintype "bidirectional"))
      (node (ref "R38") (pin "1") (pinfunction "1_1") (pintype "passive"))
    )
    (net (code "77") (name "L34") (class "Default")
      (node (ref "B18") (pin "P$2") (pinfunction "K1_P$2") (pintype "bidirectional"))
      (node (ref "B18ALT") (pin "P$2") (pinfunction "K1_P$2") (pintype "bidirectional"))
      (node (ref "R37") (pin "1") (pinfunction "1_1") (pintype "passive"))
    )
    (net (code "78") (name "L35") (class "Default")
      (node (ref "B18") (pin "P$3") (pinfunction "K2_P$3") (pintype "bidirectional"))
      (node (ref "B18ALT") (pin "P$3") (pinfunction "K2_P$3") (pintype "bidirectional"))
      (node (ref "R36") (pin "1") (pinfunction "1_1") (pintype "passive"))
    )
    (net (code "79") (name "L36") (class "Default")
      (node (ref "B19") (pin "P$2") (pinfunction "K1_P$2") (pintype "bidirectional"))
      (node (ref "B19ALT") (pin "P$2") (pinfunction "K1_P$2") (pintype "bidirectional"))
      (node (ref "R35") (pin "1") (pinfunction "1_1") (pintype "passive"))
    )
    (net (code "80") (name "L37") (class "Default")
      (node (ref "B19") (pin "P$3") (pinfunction "K2_P$3") (pintype "bidirectional"))
      (node (ref "B19ALT") (pin "P$3") (pinfunction "K2_P$3") (pintype "bidirectional"))
      (node (ref "R34") (pin "1") (pinfunction "1_1") (pintype "passive"))
    )
    (net (code "81") (name "L38") (class "Default")
      (node (ref "B20") (pin "P$2") (pinfunction "K1_P$2") (pintype "bidirectional"))
      (node (ref "B20ALT") (pin "P$2") (pinfunction "K1_P$2") (pintype "bidirectional"))
      (node (ref "R26") (pin "1") (pinfunction "1_1") (pintype "passive"))
    )
    (net (code "82") (name "L39") (class "Default")
      (node (ref "B20") (pin "P$3") (pinfunction "K2_P$3") (pintype "bidirectional"))
      (node (ref "B20ALT") (pin "P$3") (pinfunction "K2_P$3") (pintype "bidirectional"))
      (node (ref "R25") (pin "1") (pinfunction "1_1") (pintype "passive"))
    )
    (net (code "83") (name "L40") (class "Default")
      (node (ref "B21") (pin "P$2") (pinfunction "K1_P$2") (pintype "bidirectional"))
      (node (ref "R24") (pin "1") (pinfunction "1_1") (pintype "passive"))
    )
    (net (code "84") (name "L41") (class "Default")
      (node (ref "B21") (pin "P$3") (pinfunction "K2_P$3") (pintype "bidirectional"))
      (node (ref "R23") (pin "1") (pinfunction "1_1") (pintype "passive"))
    )
    (net (code "85") (name "L42") (class "Default")
      (node (ref "B22") (pin "P$2") (pinfunction "K1_P$2") (pintype "bidirectional"))
      (node (ref "R22") (pin "1") (pinfunction "1_1") (pintype "passive"))
    )
    (net (code "86") (name "L43") (class "Default")
      (node (ref "B22") (pin "P$3") (pinfunction "K2_P$3") (pintype "bidirectional"))
      (node (ref "R21") (pin "1") (pinfunction "1_1") (pintype "passive"))
    )
    (net (code "87") (name "L44") (class "Default")
      (node (ref "B23") (pin "P$2") (pinfunction "K1_P$2") (pintype "bidirectional"))
      (node (ref "B23ALT") (pin "P$2") (pinfunction "K1_P$2") (pintype "bidirectional"))
      (node (ref "R4") (pin "1") (pinfunction "1_1") (pintype "passive"))
    )
    (net (code "88") (name "L45") (class "Default")
      (node (ref "B23") (pin "P$3") (pinfunction "K2_P$3") (pintype "bidirectional"))
      (node (ref "B23ALT") (pin "P$3") (pinfunction "K2_P$3") (pintype "bidirectional"))
      (node (ref "R3") (pin "1") (pinfunction "1_1") (pintype "passive"))
    )
    (net (code "89") (name "L46") (class "Default")
      (node (ref "B24") (pin "P$2") (pinfunction "K1_P$2") (pintype "bidirectional"))
      (node (ref "B24ALT") (pin "P$2") (pinfunction "K1_P$2") (pintype "bidirectional"))
      (node (ref "R2") (pin "1") (pinfunction "1_1") (pintype "passive"))
    )
    (net (code "90") (name "L47") (class "Default")
      (node (ref "B24") (pin "P$3") (pinfunction "K2_P$3") (pintype "bidirectional"))
      (node (ref "B24ALT") (pin "P$3") (pinfunction "K2_P$3") (pintype "bidirectional"))
      (node (ref "R1") (pin "1") (pinfunction "1_1") (pintype "passive"))
    )
    (net (code "91") (name "L48") (class "Default")
      (node (ref "B25") (pin "P$2") (pinfunction "K1_P$2") (pintype "bidirectional"))
      (node (ref "B25ALT") (pin "P$2") (pinfunction "K1_P$2") (pintype "bidirectional"))
      (node (ref "R55") (pin "1") (pinfunction "1_1") (pintype "passive"))
    )
    (net (code "92") (name "L49") (class "Default")
      (node (ref "B25") (pin "P$3") (pinfunction "K2_P$3") (pintype "bidirectional"))
      (node (ref "B25ALT") (pin "P$3") (pinfunction "K2_P$3") (pintype "bidirectional"))
      (node (ref "R54") (pin "1") (pinfunction "1_1") (pintype "passive"))
    )
    (net (code "93") (name "L50") (class "Default")
      (node (ref "B26") (pin "P$2") (pinfunction "K1_P$2") (pintype "bidirectional"))
      (node (ref "B26ALT") (pin "P$2") (pinfunction "K1_P$2") (pintype "bidirectional"))
      (node (ref "R53") (pin "1") (pinfunction "1_1") (pintype "passive"))
    )
    (net (code "94") (name "L51") (class "Default")
      (node (ref "B26") (pin "P$3") (pinfunction "K2_P$3") (pintype "bidirectional"))
      (node (ref "B26ALT") (pin "P$3") (pinfunction "K2_P$3") (pintype "bidirectional"))
      (node (ref "R52") (pin "1") (pinfunction "1_1") (pintype "passive"))
    )
    (net (code "95") (name "L52") (class "Default")
      (node (ref "B27") (pin "P$2") (pinfunction "K1_P$2") (pintype "bidirectional"))
      (node (ref "B27ALT") (pin "P$2") (pinfunction "K1_P$2") (pintype "bidirectional"))
      (node (ref "R51") (pin "1") (pinfunction "1_1") (pintype "passive"))
    )
    (net (code "96") (name "L53") (class "Default")
      (node (ref "B27") (pin "P$3") (pinfunction "K2_P$3") (pintype "bidirectional"))
      (node (ref "B27ALT") (pin "P$3") (pinfunction "K2_P$3") (pintype "bidirectional"))
      (node (ref "R50") (pin "1") (pinfunction "1_1") (pintype "passive"))
    )
    (net (code "97") (name "L54") (class "Default")
      (node (ref "B28") (pin "P$2") (pinfunction "K1_P$2") (pintype "bidirectional"))
      (node (ref "B28ALT") (pin "P$2") (pinfunction "K1_P$2") (pintype "bidirectional"))
      (node (ref "R49") (pin "1") (pinfunction "1_1") (pintype "passive"))
    )
    (net (code "98") (name "L55") (class "Default")
      (node (ref "B28") (pin "P$3") (pinfunction "K2_P$3") (pintype "bidirectional"))
      (node (ref "B28ALT") (pin "P$3") (pinfunction "K2_P$3") (pintype "bidirectional"))
      (node (ref "R48") (pin "1") (pinfunction "1_1") (pintype "passive"))
    )
    (net (code "99") (name "L56") (class "Default")
      (node (ref "B29") (pin "P$2") (pinfunction "K1_P$2") (pintype "bidirectional"))
      (node (ref "B29ALT") (pin "P$2") (pinfunction "K1_P$2") (pintype "bidirectional"))
      (node (ref "R47") (pin "1") (pinfunction "1_1") (pintype "passive"))
    )
    (net (code "100") (name "L57") (class "Default")
      (node (ref "B29") (pin "P$3") (pinfunction "K2_P$3") (pintype "bidirectional"))
      (node (ref "B29ALT") (pin "P$3") (pinfunction "K2_P$3") (pintype "bidirectional"))
      (node (ref "R46") (pin "1") (pinfunction "1_1") (pintype "passive"))
    )
    (net (code "101") (name "L58") (class "Default")
      (node (ref "B30") (pin "P$2") (pinfunction "K1_P$2") (pintype "bidirectional"))
      (node (ref "B30ALT") (pin "P$2") (pinfunction "K1_P$2") (pintype "bidirectional"))
      (node (ref "R45") (pin "1") (pinfunction "1_1") (pintype "passive"))
    )
    (net (code "102") (name "L59") (class "Default")
      (node (ref "B30") (pin "P$3") (pinfunction "K2_P$3") (pintype "bidirectional"))
      (node (ref "B30ALT") (pin "P$3") (pinfunction "K2_P$3") (pintype "bidirectional"))
      (node (ref "R44") (pin "1") (pinfunction "1_1") (pintype "passive"))
    )
    (net (code "103") (name "L60") (class "Default")
      (node (ref "B31") (pin "P$2") (pinfunction "K1_P$2") (pintype "bidirectional"))
      (node (ref "B31ALT") (pin "P$2") (pinfunction "K1_P$2") (pintype "bidirectional"))
      (node (ref "R43") (pin "1") (pinfunction "1_1") (pintype "passive"))
    )
    (net (code "104") (name "L61") (class "Default")
      (node (ref "B31") (pin "P$3") (pinfunction "K2_P$3") (pintype "bidirectional"))
      (node (ref "B31ALT") (pin "P$3") (pinfunction "K2_P$3") (pintype "bidirectional"))
      (node (ref "R42") (pin "1") (pinfunction "1_1") (pintype "passive"))
    )
    (net (code "105") (name "L62") (class "Default")
      (node (ref "B32") (pin "P$2") (pinfunction "K1_P$2") (pintype "bidirectional"))
      (node (ref "B32ALT") (pin "P$2") (pinfunction "K1_P$2") (pintype "bidirectional"))
      (node (ref "R41") (pin "1") (pinfunction "1_1") (pintype "passive"))
    )
    (net (code "106") (name "L63") (class "Default")
      (node (ref "B32") (pin "P$3") (pinfunction "K2_P$3") (pintype "bidirectional"))
      (node (ref "B32ALT") (pin "P$3") (pinfunction "K2_P$3") (pintype "bidirectional"))
      (node (ref "R40") (pin "1") (pinfunction "1_1") (pintype "passive"))
    )
    (net (code "107") (name "MOSI") (class "Default")
      (node (ref "SERIAL") (pin "8") (pinfunction "8_8") (pintype "passive"))
      (node (ref "SSW1") (pin "6") (pinfunction "SDI_6") (pintype "bidirectional"))
      (node (ref "U$94") (pin "P$8") (pinfunction "8_P$8") (pintype "passive"))
    )
    (net (code "108") (name "Net-(IC2-L0)") (class "Default")
      (node (ref "IC2") (pin "6") (pinfunction "L0_6") (pintype "output"))
      (node (ref "R20") (pin "2") (pinfunction "2_2") (pintype "passive"))
    )
    (net (code "109") (name "Net-(IC2-L1)") (class "Default")
      (node (ref "IC2") (pin "7") (pinfunction "L1_7") (pintype "output"))
      (node (ref "R19") (pin "2") (pinfunction "2_2") (pintype "passive"))
    )
    (net (code "110") (name "Net-(IC2-L2)") (class "Default")
      (node (ref "IC2") (pin "8") (pinfunction "L2_8") (pintype "output"))
      (node (ref "R18") (pin "2") (pinfunction "2_2") (pintype "passive"))
    )
    (net (code "111") (name "Net-(IC2-L3)") (class "Default")
      (node (ref "IC2") (pin "9") (pinfunction "L3_9") (pintype "output"))
      (node (ref "R17") (pin "2") (pinfunction "2_2") (pintype "passive"))
    )
    (net (code "112") (name "Net-(IC2-L4)") (class "Default")
      (node (ref "IC2") (pin "10") (pinfunction "L4_10") (pintype "output"))
      (node (ref "R16") (pin "2") (pinfunction "2_2") (pintype "passive"))
    )
    (net (code "113") (name "Net-(IC2-L5)") (class "Default")
      (node (ref "IC2") (pin "11") (pinfunction "L5_11") (pintype "output"))
      (node (ref "R15") (pin "2") (pinfunction "2_2") (pintype "passive"))
    )
    (net (code "114") (name "Net-(IC2-L6)") (class "Default")
      (node (ref "IC2") (pin "12") (pinfunction "L6_12") (pintype "output"))
      (node (ref "R14") (pin "2") (pinfunction "2_2") (pintype "passive"))
    )
    (net (code "115") (name "Net-(IC2-L7)") (class "Default")
      (node (ref "IC2") (pin "13") (pinfunction "L7_13") (pintype "output"))
      (node (ref "R13") (pin "2") (pinfunction "2_2") (pintype "passive"))
    )
    (net (code "116") (name "Net-(IC2-L8)") (class "Default")
      (node (ref "IC2") (pin "15") (pinfunction "L8_15") (pintype "output"))
      (node (ref "R12") (pin "2") (pinfunction "2_2") (pintype "passive"))
    )
    (net (code "117") (name "Net-(IC2-L9)") (class "Default")
      (node (ref "IC2") (pin "16") (pinfunction "L9_16") (pintype "output"))
      (node (ref "R11") (pin "2") (pinfunction "2_2") (pintype "passive"))
    )
    (net (code "118") (name "Net-(IC2-L10)") (class "Default")
      (node (ref "IC2") (pin "17") (pinfunction "L10_17") (pintype "output"))
      (node (ref "R10") (pin "2") (pinfunction "2_2") (pintype "passive"))
    )
    (net (code "119") (name "Net-(IC2-L11)") (class "Default")
      (node (ref "IC2") (pin "18") (pinfunction "L11_18") (pintype "output"))
      (node (ref "R9") (pin "2") (pinfunction "2_2") (pintype "passive"))
    )
    (net (code "120") (name "Net-(IC2-L12)") (class "Default")
      (node (ref "IC2") (pin "19") (pinfunction "L12_19") (pintype "output"))
      (node (ref "R8") (pin "2") (pinfunction "2_2") (pintype "passive"))
    )
    (net (code "121") (name "Net-(IC2-L13)") (class "Default")
      (node (ref "IC2") (pin "20") (pinfunction "L13_20") (pintype "output"))
      (node (ref "R7") (pin "2") (pinfunction "2_2") (pintype "passive"))
    )
    (net (code "122") (name "Net-(IC2-L14)") (class "Default")
      (node (ref "IC2") (pin "21") (pinfunction "L14_21") (pintype "output"))
      (node (ref "R6") (pin "2") (pinfunction "2_2") (pintype "passive"))
    )
    (net (code "123") (name "Net-(IC2-L15)") (class "Default")
      (node (ref "IC2") (pin "22") (pinfunction "L15_22") (pintype "output"))
      (node (ref "R5") (pin "2") (pinfunction "2_2") (pintype "passive"))
    )
    (net (code "124") (name "Net-(IC3-L0)") (class "Default")
      (node (ref "IC3") (pin "6") (pinfunction "L0_6") (pintype "output"))
      (node (ref "R32") (pin "2") (pinfunction "2_2") (pintype "passive"))
    )
    (net (code "125") (name "Net-(IC3-L1)") (class "Default")
      (node (ref "IC3") (pin "7") (pinfunction "L1_7") (pintype "output"))
      (node (ref "R31") (pin "2") (pinfunction "2_2") (pintype "passive"))
    )
    (net (code "126") (name "Net-(IC3-L2)") (class "Default")
      (node (ref "IC3") (pin "8") (pinfunction "L2_8") (pintype "output"))
      (node (ref "R30") (pin "2") (pinfunction "2_2") (pintype "passive"))
    )
    (net (code "127") (name "Net-(IC3-L3)") (class "Default")
      (node (ref "IC3") (pin "9") (pinfunction "L3_9") (pintype "output"))
      (node (ref "R29") (pin "2") (pinfunction "2_2") (pintype "passive"))
    )
    (net (code "128") (name "Net-(IC3-L4)") (class "Default")
      (node (ref "IC3") (pin "10") (pinfunction "L4_10") (pintype "output"))
      (node (ref "R28") (pin "2") (pinfunction "2_2") (pintype "passive"))
    )
    (net (code "129") (name "Net-(IC3-L5)") (class "Default")
      (node (ref "IC3") (pin "11") (pinfunction "L5_11") (pintype "output"))
      (node (ref "R27") (pin "2") (pinfunction "2_2") (pintype "passive"))
    )
    (net (code "130") (name "Net-(IC3-L6)") (class "Default")
      (node (ref "IC3") (pin "12") (pinfunction "L6_12") (pintype "output"))
      (node (ref "R57") (pin "2") (pinfunction "2_2") (pintype "passive"))
    )
    (net (code "131") (name "Net-(IC3-L7)") (class "Default")
      (node (ref "IC3") (pin "13") (pinfunction "L7_13") (pintype "output"))
      (node (ref "R56") (pin "2") (pinfunction "2_2") (pintype "passive"))
    )
    (net (code "132") (name "Net-(IC3-L8)") (class "Default")
      (node (ref "IC3") (pin "15") (pinfunction "L8_15") (pintype "output"))
      (node (ref "R63") (pin "2") (pinfunction "2_2") (pintype "passive"))
    )
    (net (code "133") (name "Net-(IC3-L9)") (class "Default")
      (node (ref "IC3") (pin "16") (pinfunction "L9_16") (pintype "output"))
      (node (ref "R62") (pin "2") (pinfunction "2_2") (pintype "passive"))
    )
    (net (code "134") (name "Net-(IC3-L10)") (class "Default")
      (node (ref "IC3") (pin "17") (pinfunction "L10_17") (pintype "output"))
      (node (ref "R61") (pin "2") (pinfunction "2_2") (pintype "passive"))
    )
    (net (code "135") (name "Net-(IC3-L11)") (class "Default")
      (node (ref "IC3") (pin "18") (pinfunction "L11_18") (pintype "output"))
      (node (ref "R60") (pin "2") (pinfunction "2_2") (pintype "passive"))
    )
    (net (code "136") (name "Net-(IC3-L12)") (class "Default")
      (node (ref "IC3") (pin "19") (pinfunction "L12_19") (pintype "output"))
      (node (ref "R59") (pin "2") (pinfunction "2_2") (pintype "passive"))
    )
    (net (code "137") (name "Net-(IC3-L13)") (class "Default")
      (node (ref "IC3") (pin "20") (pinfunction "L13_20") (pintype "output"))
      (node (ref "R58") (pin "2") (pinfunction "2_2") (pintype "passive"))
    )
    (net (code "138") (name "Net-(IC3-L14)") (class "Default")
      (node (ref "IC3") (pin "21") (pinfunction "L14_21") (pintype "output"))
      (node (ref "R65") (pin "2") (pinfunction "2_2") (pintype "passive"))
    )
    (net (code "139") (name "Net-(IC3-L15)") (class "Default")
      (node (ref "IC3") (pin "22") (pinfunction "L15_22") (pintype "output"))
      (node (ref "R64") (pin "2") (pinfunction "2_2") (pintype "passive"))
    )
    (net (code "140") (name "Net-(IC5A-I)") (class "Default")
      (node (ref "C10") (pin "1") (pinfunction "1_1") (pintype "passive"))
      (node (ref "IC5") (pin "13") (pinfunction "I_13") (pintype "input"))
      (node (ref "R33") (pin "1") (pinfunction "1_1") (pintype "passive"))
      (node (ref "SW1") (pin "B") (pinfunction "B_B") (pintype "passive"))
    )
    (net (code "141") (name "Net-(IC6-L0)") (class "Default")
      (node (ref "IC6") (pin "6") (pinfunction "L0_6") (pintype "output"))
      (node (ref "R39") (pin "2") (pinfunction "2_2") (pintype "passive"))
    )
    (net (code "142") (name "Net-(IC6-L1)") (class "Default")
      (node (ref "IC6") (pin "7") (pinfunction "L1_7") (pintype "output"))
      (node (ref "R38") (pin "2") (pinfunction "2_2") (pintype "passive"))
    )
    (net (code "143") (name "Net-(IC6-L2)") (class "Default")
      (node (ref "IC6") (pin "8") (pinfunction "L2_8") (pintype "output"))
      (node (ref "R37") (pin "2") (pinfunction "2_2") (pintype "passive"))
    )
    (net (code "144") (name "Net-(IC6-L3)") (class "Default")
      (node (ref "IC6") (pin "9") (pinfunction "L3_9") (pintype "output"))
      (node (ref "R36") (pin "2") (pinfunction "2_2") (pintype "passive"))
    )
    (net (code "145") (name "Net-(IC6-L4)") (class "Default")
      (node (ref "IC6") (pin "10") (pinfunction "L4_10") (pintype "output"))
      (node (ref "R35") (pin "2") (pinfunction "2_2") (pintype "passive"))
    )
    (net (code "146") (name "Net-(IC6-L5)") (class "Default")
      (node (ref "IC6") (pin "11") (pinfunction "L5_11") (pintype "output"))
      (node (ref "R34") (pin "2") (pinfunction "2_2") (pintype "passive"))
    )
    (net (code "147") (name "Net-(IC6-L6)") (class "Default")
      (node (ref "IC6") (pin "12") (pinfunction "L6_12") (pintype "output"))
      (node (ref "R26") (pin "2") (pinfunction "2_2") (pintype "passive"))
    )
    (net (code "148") (name "Net-(IC6-L7)") (class "Default")
      (node (ref "IC6") (pin "13") (pinfunction "L7_13") (pintype "output"))
      (node (ref "R25") (pin "2") (pinfunction "2_2") (pintype "passive"))
    )
    (net (code "149") (name "Net-(IC6-L8)") (class "Default")
      (node (ref "IC6") (pin "15") (pinfunction "L8_15") (pintype "output"))
      (node (ref "R24") (pin "2") (pinfunction "2_2") (pintype "passive"))
    )
    (net (code "150") (name "Net-(IC6-L9)") (class "Default")
      (node (ref "IC6") (pin "16") (pinfunction "L9_16") (pintype "output"))
      (node (ref "R23") (pin "2") (pinfunction "2_2") (pintype "passive"))
    )
    (net (code "151") (name "Net-(IC6-L10)") (class "Default")
      (node (ref "IC6") (pin "17") (pinfunction "L10_17") (pintype "output"))
      (node (ref "R22") (pin "2") (pinfunction "2_2") (pintype "passive"))
    )
    (net (code "152") (name "Net-(IC6-L11)") (class "Default")
      (node (ref "IC6") (pin "18") (pinfunction "L11_18") (pintype "output"))
      (node (ref "R21") (pin "2") (pinfunction "2_2") (pintype "passive"))
    )
    (net (code "153") (name "Net-(IC6-L12)") (class "Default")
      (node (ref "IC6") (pin "19") (pinfunction "L12_19") (pintype "output"))
      (node (ref "R4") (pin "2") (pinfunction "2_2") (pintype "passive"))
    )
    (net (code "154") (name "Net-(IC6-L13)") (class "Default")
      (node (ref "IC6") (pin "20") (pinfunction "L13_20") (pintype "output"))
      (node (ref "R3") (pin "2") (pinfunction "2_2") (pintype "passive"))
    )
    (net (code "155") (name "Net-(IC6-L14)") (class "Default")
      (node (ref "IC6") (pin "21") (pinfunction "L14_21") (pintype "output"))
      (node (ref "R2") (pin "2") (pinfunction "2_2") (pintype "passive"))
    )
    (net (code "156") (name "Net-(IC6-L15)") (class "Default")
      (node (ref "IC6") (pin "22") (pinfunction "L15_22") (pintype "output"))
      (node (ref "R1") (pin "2") (pinfunction "2_2") (pintype "passive"))
    )
    (net (code "157") (name "Net-(IC8-L0)") (class "Default")
      (node (ref "IC8") (pin "6") (pinfunction "L0_6") (pintype "output"))
      (node (ref "R55") (pin "2") (pinfunction "2_2") (pintype "passive"))
    )
    (net (code "158") (name "Net-(IC8-L1)") (class "Default")
      (node (ref "IC8") (pin "7") (pinfunction "L1_7") (pintype "output"))
      (node (ref "R54") (pin "2") (pinfunction "2_2") (pintype "passive"))
    )
    (net (code "159") (name "Net-(IC8-L2)") (class "Default")
      (node (ref "IC8") (pin "8") (pinfunction "L2_8") (pintype "output"))
      (node (ref "R53") (pin "2") (pinfunction "2_2") (pintype "passive"))
    )
    (net (code "160") (name "Net-(IC8-L3)") (class "Default")
      (node (ref "IC8") (pin "9") (pinfunction "L3_9") (pintype "output"))
      (node (ref "R52") (pin "2") (pinfunction "2_2") (pintype "passive"))
    )
    (net (code "161") (name "Net-(IC8-L4)") (class "Default")
      (node (ref "IC8") (pin "10") (pinfunction "L4_10") (pintype "output"))
      (node (ref "R51") (pin "2") (pinfunction "2_2") (pintype "passive"))
    )
    (net (code "162") (name "Net-(IC8-L5)") (class "Default")
      (node (ref "IC8") (pin "11") (pinfunction "L5_11") (pintype "output"))
      (node (ref "R50") (pin "2") (pinfunction "2_2") (pintype "passive"))
    )
    (net (code "163") (name "Net-(IC8-L6)") (class "Default")
      (node (ref "IC8") (pin "12") (pinfunction "L6_12") (pintype "output"))
      (node (ref "R49") (pin "2") (pinfunction "2_2") (pintype "passive"))
    )
    (net (code "164") (name "Net-(IC8-L7)") (class "Default")
      (node (ref "IC8") (pin "13") (pinfunction "L7_13") (pintype "output"))
      (node (ref "R48") (pin "2") (pinfunction "2_2") (pintype "passive"))
    )
    (net (code "165") (name "Net-(IC8-L8)") (class "Default")
      (node (ref "IC8") (pin "15") (pinfunction "L8_15") (pintype "output"))
      (node (ref "R47") (pin "2") (pinfunction "2_2") (pintype "passive"))
    )
    (net (code "166") (name "Net-(IC8-L9)") (class "Default")
      (node (ref "IC8") (pin "16") (pinfunction "L9_16") (pintype "output"))
      (node (ref "R46") (pin "2") (pinfunction "2_2") (pintype "passive"))
    )
    (net (code "167") (name "Net-(IC8-L10)") (class "Default")
      (node (ref "IC8") (pin "17") (pinfunction "L10_17") (pintype "output"))
      (node (ref "R45") (pin "2") (pinfunction "2_2") (pintype "passive"))
    )
    (net (code "168") (name "Net-(IC8-L11)") (class "Default")
      (node (ref "IC8") (pin "18") (pinfunction "L11_18") (pintype "output"))
      (node (ref "R44") (pin "2") (pinfunction "2_2") (pintype "passive"))
    )
    (net (code "169") (name "Net-(IC8-L12)") (class "Default")
      (node (ref "IC8") (pin "19") (pinfunction "L12_19") (pintype "output"))
      (node (ref "R43") (pin "2") (pinfunction "2_2") (pintype "passive"))
    )
    (net (code "170") (name "Net-(IC8-L13)") (class "Default")
      (node (ref "IC8") (pin "20") (pinfunction "L13_20") (pintype "output"))
      (node (ref "R42") (pin "2") (pinfunction "2_2") (pintype "passive"))
    )
    (net (code "171") (name "Net-(IC8-L14)") (class "Default")
      (node (ref "IC8") (pin "21") (pinfunction "L14_21") (pintype "output"))
      (node (ref "R41") (pin "2") (pinfunction "2_2") (pintype "passive"))
    )
    (net (code "172") (name "Net-(IC8-L15)") (class "Default")
      (node (ref "IC8") (pin "22") (pinfunction "L15_22") (pintype "output"))
      (node (ref "R40") (pin "2") (pinfunction "2_2") (pintype "passive"))
    )
    (net (code "173") (name "SCLK") (class "Default")
      (node (ref "SERIAL") (pin "7") (pinfunction "7_7") (pintype "passive"))
      (node (ref "SSW1") (pin "7") (pinfunction "SCK_7") (pintype "bidirectional"))
      (node (ref "U$94") (pin "P$7") (pinfunction "7_P$7") (pintype "passive"))
    )
    (net (code "174") (name "unconnected-(IC1-INTA-Pad20)") (class "Default")
      (node (ref "IC1") (pin "20") (pinfunction "INTA_20") (pintype "output"))
    )
    (net (code "175") (name "unconnected-(IC1-INTB-Pad19)") (class "Default")
      (node (ref "IC1") (pin "19") (pinfunction "INTB_19") (pintype "output"))
    )
    (net (code "176") (name "unconnected-(IC4-GPA2-Pad23)") (class "Default")
      (node (ref "IC4") (pin "23") (pinfunction "GPA2_23") (pintype "bidirectional"))
    )
    (net (code "177") (name "unconnected-(IC4-GPA3-Pad24)") (class "Default")
      (node (ref "IC4") (pin "24") (pinfunction "GPA3_24") (pintype "bidirectional"))
    )
    (net (code "178") (name "unconnected-(IC4-GPA5-Pad26)") (class "Default")
      (node (ref "IC4") (pin "26") (pinfunction "GPA5_26") (pintype "bidirectional"))
    )
    (net (code "179") (name "unconnected-(IC4-GPA6-Pad27)") (class "Default")
      (node (ref "IC4") (pin "27") (pinfunction "GPA6_27") (pintype "bidirectional"))
    )
    (net (code "180") (name "unconnected-(IC4-GPA7-Pad28)") (class "Default")
      (node (ref "IC4") (pin "28") (pinfunction "GPA7_28") (pintype "bidirectional"))
    )
    (net (code "181") (name "unconnected-(IC4-GPB1-Pad2)") (class "Default")
      (node (ref "IC4") (pin "2") (pinfunction "GPB1_2") (pintype "bidirectional"))
    )
    (net (code "182") (name "unconnected-(IC4-GPB2-Pad3)") (class "Default")
      (node (ref "IC4") (pin "3") (pinfunction "GPB2_3") (pintype "bidirectional"))
    )
    (net (code "183") (name "unconnected-(IC4-GPB3-Pad4)") (class "Default")
      (node (ref "IC4") (pin "4") (pinfunction "GPB3_4") (pintype "bidirectional"))
    )
    (net (code "184") (name "unconnected-(IC4-GPB5-Pad6)") (class "Default")
      (node (ref "IC4") (pin "6") (pinfunction "GPB5_6") (pintype "bidirectional"))
    )
    (net (code "185") (name "unconnected-(IC4-GPB6-Pad7)") (class "Default")
      (node (ref "IC4") (pin "7") (pinfunction "GPB6_7") (pintype "bidirectional"))
    )
    (net (code "186") (name "unconnected-(IC4-GPB7-Pad8)") (class "Default")
      (node (ref "IC4") (pin "8") (pinfunction "GPB7_8") (pintype "bidirectional"))
    )
    (net (code "187") (name "unconnected-(IC4-INTA-Pad20)") (class "Default")
      (node (ref "IC4") (pin "20") (pinfunction "INTA_20") (pintype "output"))
    )
    (net (code "188") (name "unconnected-(IC4-INTB-Pad19)") (class "Default")
      (node (ref "IC4") (pin "19") (pinfunction "INTB_19") (pintype "output"))
    )
    (net (code "189") (name "unconnected-(IC5B-O-Pad10)") (class "Default")
      (node (ref "IC5") (pin "10") (pinfunction "O_10") (pintype "output"))
    )
    (net (code "190") (name "unconnected-(IC5C-O-Pad8)") (class "Default")
      (node (ref "IC5") (pin "8") (pinfunction "O_8") (pintype "output"))
    )
    (net (code "191") (name "unconnected-(IC5D-O-Pad2)") (class "Default")
      (node (ref "IC5") (pin "2") (pinfunction "O_2") (pintype "output"))
    )
    (net (code "192") (name "unconnected-(IC5E-O-Pad4)") (class "Default")
      (node (ref "IC5") (pin "4") (pinfunction "O_4") (pintype "output"))
    )
    (net (code "193") (name "unconnected-(IC5F-O-Pad6)") (class "Default")
      (node (ref "IC5") (pin "6") (pinfunction "O_6") (pintype "output"))
    )
    (net (code "194") (name "unconnected-(IC7-INTA-Pad20)") (class "Default")
      (node (ref "IC7") (pin "20") (pinfunction "INTA_20") (pintype "output"))
    )
    (net (code "195") (name "unconnected-(IC7-INTB-Pad19)") (class "Default")
      (node (ref "IC7") (pin "19") (pinfunction "INTB_19") (pintype "output"))
    )
    (net (code "196") (name "unconnected-(SERIAL-Pad6)") (class "Default")
      (node (ref "SERIAL") (pin "6") (pinfunction "6_6") (pintype "passive"))
    )
    (net (code "197") (name "unconnected-(SSW1-SDO-Pad5)") (class "Default")
      (node (ref "SSW1") (pin "5") (pinfunction "SDO_5") (pintype "bidirectional"))
    )
    (net (code "198") (name "unconnected-(U$94-5-PadP$5)") (class "Default")
      (node (ref "U$94") (pin "P$5") (pinfunction "5_P$5") (pintype "passive"))
    )
    (net (code "199") (name "unconnected-(U$94-6-PadP$6)") (class "Default")
      (node (ref "U$94") (pin "P$6") (pinfunction "6_P$6") (pintype "passive"))
    )
  )
)
